# main.net
KiCad netlist of a schematic drawn in EAGLE
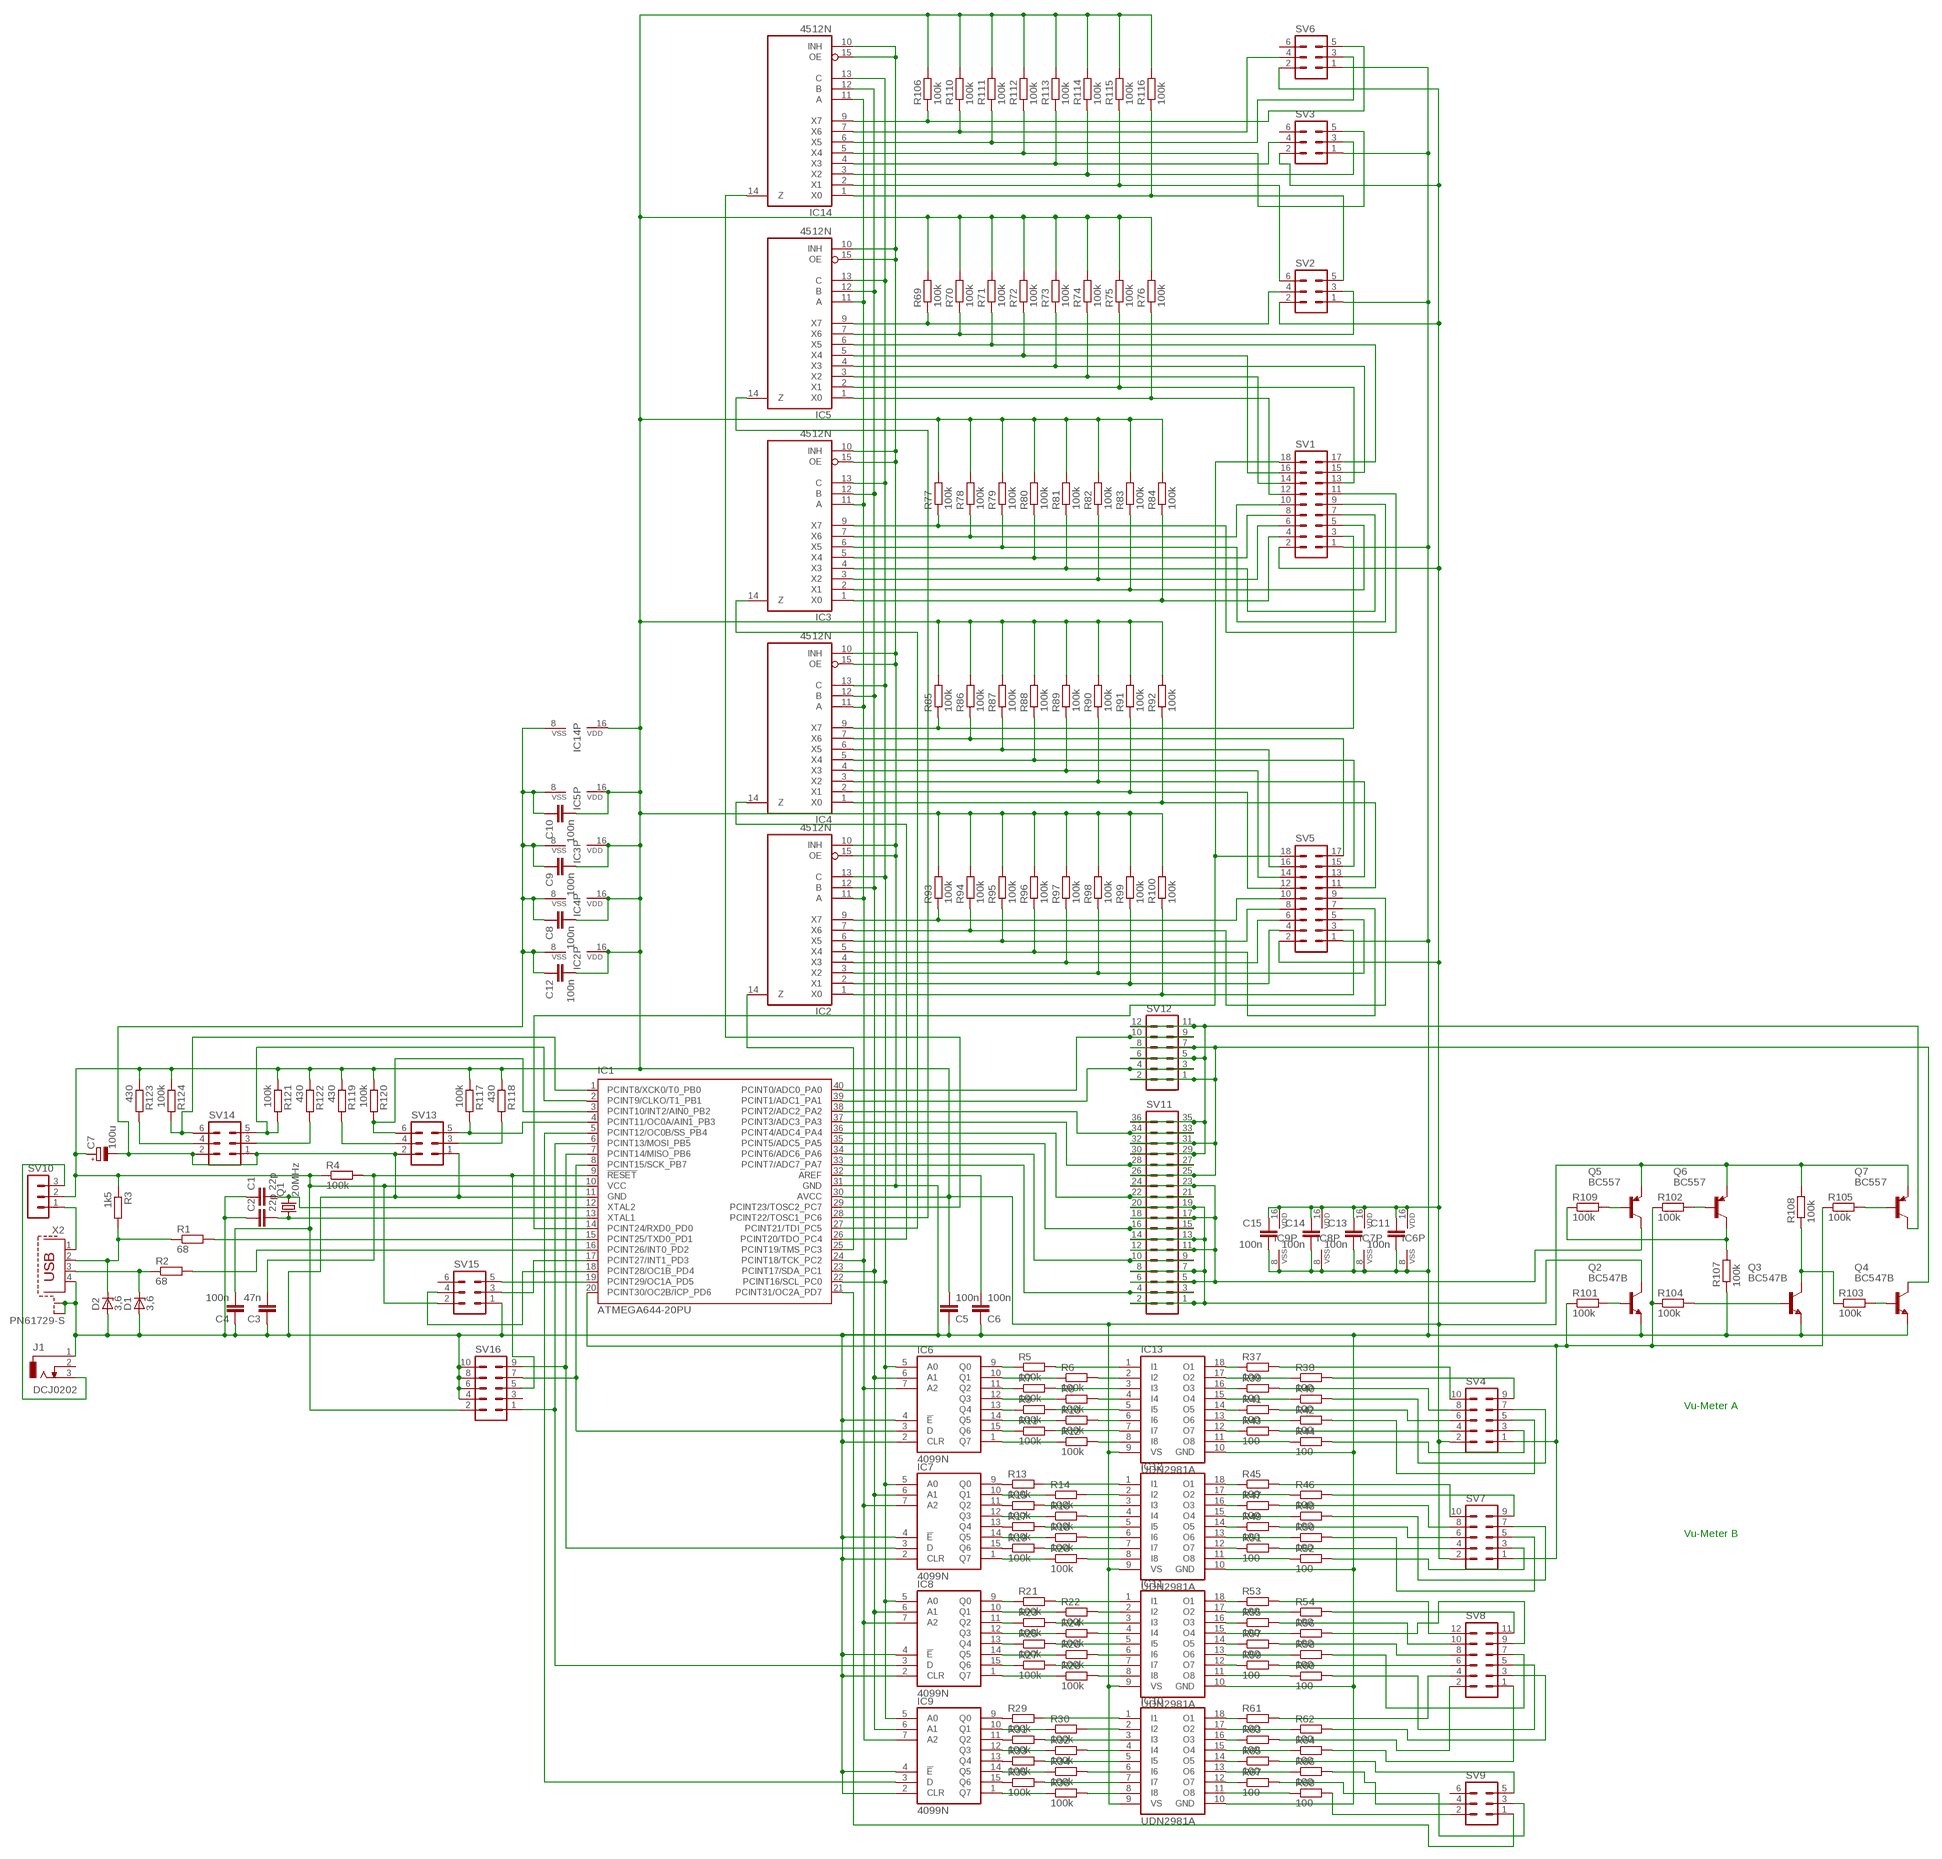
[diagram p0: schematic, sheet 1]

(export (version "E")
  (design (tool "Eeschema 10.0.6"))
  (components
    (comp (ref "C1")
      (value "22p")
      (footprint "eagle-import:C025-024X044")
      (libsource (lib "eagle-import") (part "C-EU025-024X044"))
    )
    (comp (ref "C2")
      (value "22p")
      (footprint "eagle-import:C025-024X044")
      (libsource (lib "eagle-import") (part "C-EU025-024X044"))
    )
    (comp (ref "C3")
      (value "47n")
      (footprint "eagle-import:C025-024X044")
      (libsource (lib "eagle-import") (part "C-EU025-024X044"))
    )
    (comp (ref "C4")
      (value "100n")
      (footprint "eagle-import:C025-024X044")
      (libsource (lib "eagle-import") (part "C-EU025-024X044"))
    )
    (comp (ref "C5")
      (value "100n")
      (footprint "eagle-import:C025-024X044")
      (libsource (lib "eagle-import") (part "C-EU025-024X044"))
    )
    (comp (ref "C6")
      (value "100n")
      (footprint "eagle-import:C025-024X044")
      (libsource (lib "eagle-import") (part "C-EU025-024X044"))
    )
    (comp (ref "C7")
      (value "100u")
      (footprint "eagle-import:E3,5-8")
      (libsource (lib "eagle-import") (part "CPOL-EUE3.5-8"))
    )
    (comp (ref "C8")
      (value "100n")
      (footprint "eagle-import:C025-024X044")
      (libsource (lib "eagle-import") (part "C-EU025-024X044"))
    )
    (comp (ref "C9")
      (value "100n")
      (footprint "eagle-import:C025-024X044")
      (libsource (lib "eagle-import") (part "C-EU025-024X044"))
    )
    (comp (ref "C10")
      (value "100n")
      (footprint "eagle-import:C025-024X044")
      (libsource (lib "eagle-import") (part "C-EU025-024X044"))
    )
    (comp (ref "C11")
      (value "100n")
      (footprint "eagle-import:C025-024X044")
      (libsource (lib "eagle-import") (part "C-EU025-024X044"))
    )
    (comp (ref "C12")
      (value "100n")
      (footprint "eagle-import:C025-024X044")
      (libsource (lib "eagle-import") (part "C-EU025-024X044"))
    )
    (comp (ref "C13")
      (value "100n")
      (footprint "eagle-import:C025-024X044")
      (libsource (lib "eagle-import") (part "C-EU025-024X044"))
    )
    (comp (ref "C14")
      (value "100n")
      (footprint "eagle-import:C025-024X044")
      (libsource (lib "eagle-import") (part "C-EU025-024X044"))
    )
    (comp (ref "C15")
      (value "100n")
      (footprint "eagle-import:C025-024X044")
      (libsource (lib "eagle-import") (part "C-EU025-024X044"))
    )
    (comp (ref "D1")
      (value "3,6")
      (footprint "eagle-import:DO34Z7")
      (libsource (lib "eagle-import") (part "ZENER-DIODEDO34-7"))
    )
    (comp (ref "D2")
      (value "3,6")
      (footprint "eagle-import:DO34Z7")
      (libsource (lib "eagle-import") (part "ZENER-DIODEDO34-7"))
    )
    (comp (ref "IC1")
      (value "ATMEGA644-20PU")
      (footprint "eagle-import:DIL40")
      (libsource (lib "eagle-import") (part "ATMEGA644-PU20"))
    )
    (comp (ref "IC2")
      (value "4512N")
      (footprint "eagle-import:DIL16")
      (libsource (lib "eagle-import") (part "4512N"))
    )
    (comp (ref "IC3")
      (value "4512N")
      (footprint "eagle-import:DIL16")
      (libsource (lib "eagle-import") (part "4512N"))
    )
    (comp (ref "IC4")
      (value "4512N")
      (footprint "eagle-import:DIL16")
      (libsource (lib "eagle-import") (part "4512N"))
    )
    (comp (ref "IC5")
      (value "4512N")
      (footprint "eagle-import:DIL16")
      (libsource (lib "eagle-import") (part "4512N"))
    )
    (comp (ref "IC6")
      (value "4099N")
      (footprint "eagle-import:DIL16")
      (libsource (lib "eagle-import") (part "4099N"))
    )
    (comp (ref "IC7")
      (value "4099N")
      (footprint "eagle-import:DIL16")
      (libsource (lib "eagle-import") (part "4099N"))
    )
    (comp (ref "IC8")
      (value "4099N")
      (footprint "eagle-import:DIL16")
      (libsource (lib "eagle-import") (part "4099N"))
    )
    (comp (ref "IC9")
      (value "4099N")
      (footprint "eagle-import:DIL16")
      (libsource (lib "eagle-import") (part "4099N"))
    )
    (comp (ref "IC10")
      (value "UDN2981A")
      (footprint "eagle-import:DIL18")
      (libsource (lib "eagle-import") (part "UDN298A1"))
    )
    (comp (ref "IC11")
      (value "UDN2981A")
      (footprint "eagle-import:DIL18")
      (libsource (lib "eagle-import") (part "UDN298A1"))
    )
    (comp (ref "IC12")
      (value "UDN2981A")
      (footprint "eagle-import:DIL18")
      (libsource (lib "eagle-import") (part "UDN298A1"))
    )
    (comp (ref "IC13")
      (value "UDN2981A")
      (footprint "eagle-import:DIL18")
      (libsource (lib "eagle-import") (part "UDN298A1"))
    )
    (comp (ref "IC14")
      (value "4512N")
      (footprint "eagle-import:DIL16")
      (libsource (lib "eagle-import") (part "4512N"))
    )
    (comp (ref "J1")
      (value "DCJ0202")
      (footprint "eagle-import:DCJ0202")
      (libsource (lib "eagle-import") (part "DCJ0202"))
    )
    (comp (ref "Q1")
      (value "20MHz")
      (footprint "eagle-import:HC18U-V")
      (libsource (lib "eagle-import") (part "CRYSTALHC18U-V"))
    )
    (comp (ref "Q2")
      (value "BC547B")
      (footprint "eagle-import:TO92")
      (libsource (lib "eagle-import") (part "BC547B"))
    )
    (comp (ref "Q3")
      (value "BC547B")
      (footprint "eagle-import:TO92")
      (libsource (lib "eagle-import") (part "BC547B"))
    )
    (comp (ref "Q4")
      (value "BC547B")
      (footprint "eagle-import:TO92")
      (libsource (lib "eagle-import") (part "BC547B"))
    )
    (comp (ref "Q5")
      (value "BC557")
      (footprint "eagle-import:TO92")
      (libsource (lib "eagle-import") (part "BC557"))
    )
    (comp (ref "Q6")
      (value "BC557")
      (footprint "eagle-import:TO92")
      (libsource (lib "eagle-import") (part "BC557"))
    )
    (comp (ref "Q7")
      (value "BC557")
      (footprint "eagle-import:TO92")
      (libsource (lib "eagle-import") (part "BC557"))
    )
    (comp (ref "R1")
      (value "68")
      (footprint "eagle-import:0204_7")
      (libsource (lib "eagle-import") (part "R-EU_0204/7"))
    )
    (comp (ref "R2")
      (value "68")
      (footprint "eagle-import:0204_7")
      (libsource (lib "eagle-import") (part "R-EU_0204/7"))
    )
    (comp (ref "R3")
      (value "1k5")
      (footprint "eagle-import:0204_7")
      (libsource (lib "eagle-import") (part "R-EU_0204/7"))
    )
    (comp (ref "R4")
      (value "100k")
      (footprint "eagle-import:0204_7")
      (libsource (lib "eagle-import") (part "R-EU_0204/7"))
    )
    (comp (ref "R5")
      (value "100k")
      (footprint "eagle-import:0204_7")
      (libsource (lib "eagle-import") (part "R-EU_0204/7"))
    )
    (comp (ref "R6")
      (value "100k")
      (footprint "eagle-import:0204_7")
      (libsource (lib "eagle-import") (part "R-EU_0204/7"))
    )
    (comp (ref "R7")
      (value "100k")
      (footprint "eagle-import:0204_7")
      (libsource (lib "eagle-import") (part "R-EU_0204/7"))
    )
    (comp (ref "R8")
      (value "100k")
      (footprint "eagle-import:0204_7")
      (libsource (lib "eagle-import") (part "R-EU_0204/7"))
    )
    (comp (ref "R9")
      (value "100k")
      (footprint "eagle-import:0204_7")
      (libsource (lib "eagle-import") (part "R-EU_0204/7"))
    )
    (comp (ref "R10")
      (value "100k")
      (footprint "eagle-import:0204_7")
      (libsource (lib "eagle-import") (part "R-EU_0204/7"))
    )
    (comp (ref "R11")
      (value "100k")
      (footprint "eagle-import:0204_7")
      (libsource (lib "eagle-import") (part "R-EU_0204/7"))
    )
    (comp (ref "R12")
      (value "100k")
      (footprint "eagle-import:0204_7")
      (libsource (lib "eagle-import") (part "R-EU_0204/7"))
    )
    (comp (ref "R13")
      (value "100k")
      (footprint "eagle-import:0204_7")
      (libsource (lib "eagle-import") (part "R-EU_0204/7"))
    )
    (comp (ref "R14")
      (value "100k")
      (footprint "eagle-import:0204_7")
      (libsource (lib "eagle-import") (part "R-EU_0204/7"))
    )
    (comp (ref "R15")
      (value "100k")
      (footprint "eagle-import:0204_7")
      (libsource (lib "eagle-import") (part "R-EU_0204/7"))
    )
    (comp (ref "R16")
      (value "100k")
      (footprint "eagle-import:0204_7")
      (libsource (lib "eagle-import") (part "R-EU_0204/7"))
    )
    (comp (ref "R17")
      (value "100k")
      (footprint "eagle-import:0204_7")
      (libsource (lib "eagle-import") (part "R-EU_0204/7"))
    )
    (comp (ref "R18")
      (value "100k")
      (footprint "eagle-import:0204_7")
      (libsource (lib "eagle-import") (part "R-EU_0204/7"))
    )
    (comp (ref "R19")
      (value "100k")
      (footprint "eagle-import:0204_7")
      (libsource (lib "eagle-import") (part "R-EU_0204/7"))
    )
    (comp (ref "R20")
      (value "100k")
      (footprint "eagle-import:0204_7")
      (libsource (lib "eagle-import") (part "R-EU_0204/7"))
    )
    (comp (ref "R21")
      (value "100k")
      (footprint "eagle-import:0204_7")
      (libsource (lib "eagle-import") (part "R-EU_0204/7"))
    )
    (comp (ref "R22")
      (value "100k")
      (footprint "eagle-import:0204_7")
      (libsource (lib "eagle-import") (part "R-EU_0204/7"))
    )
    (comp (ref "R23")
      (value "100k")
      (footprint "eagle-import:0204_7")
      (libsource (lib "eagle-import") (part "R-EU_0204/7"))
    )
    (comp (ref "R24")
      (value "100k")
      (footprint "eagle-import:0204_7")
      (libsource (lib "eagle-import") (part "R-EU_0204/7"))
    )
    (comp (ref "R25")
      (value "100k")
      (footprint "eagle-import:0204_7")
      (libsource (lib "eagle-import") (part "R-EU_0204/7"))
    )
    (comp (ref "R26")
      (value "100k")
      (footprint "eagle-import:0204_7")
      (libsource (lib "eagle-import") (part "R-EU_0204/7"))
    )
    (comp (ref "R27")
      (value "100k")
      (footprint "eagle-import:0204_7")
      (libsource (lib "eagle-import") (part "R-EU_0204/7"))
    )
    (comp (ref "R28")
      (value "100k")
      (footprint "eagle-import:0204_7")
      (libsource (lib "eagle-import") (part "R-EU_0204/7"))
    )
    (comp (ref "R29")
      (value "100k")
      (footprint "eagle-import:0204_7")
      (libsource (lib "eagle-import") (part "R-EU_0204/7"))
    )
    (comp (ref "R30")
      (value "100k")
      (footprint "eagle-import:0204_7")
      (libsource (lib "eagle-import") (part "R-EU_0204/7"))
    )
    (comp (ref "R31")
      (value "100k")
      (footprint "eagle-import:0204_7")
      (libsource (lib "eagle-import") (part "R-EU_0204/7"))
    )
    (comp (ref "R32")
      (value "100k")
      (footprint "eagle-import:0204_7")
      (libsource (lib "eagle-import") (part "R-EU_0204/7"))
    )
    (comp (ref "R33")
      (value "100k")
      (footprint "eagle-import:0204_7")
      (libsource (lib "eagle-import") (part "R-EU_0204/7"))
    )
    (comp (ref "R34")
      (value "100k")
      (footprint "eagle-import:0204_7")
      (libsource (lib "eagle-import") (part "R-EU_0204/7"))
    )
    (comp (ref "R35")
      (value "100k")
      (footprint "eagle-import:0204_7")
      (libsource (lib "eagle-import") (part "R-EU_0204/7"))
    )
    (comp (ref "R36")
      (value "100k")
      (footprint "eagle-import:0204_7")
      (libsource (lib "eagle-import") (part "R-EU_0204/7"))
    )
    (comp (ref "R37")
      (value "100")
      (footprint "eagle-import:0204_7")
      (libsource (lib "eagle-import") (part "R-EU_0204/7"))
    )
    (comp (ref "R38")
      (value "100")
      (footprint "eagle-import:0204_7")
      (libsource (lib "eagle-import") (part "R-EU_0204/7"))
    )
    (comp (ref "R39")
      (value "100")
      (footprint "eagle-import:0204_7")
      (libsource (lib "eagle-import") (part "R-EU_0204/7"))
    )
    (comp (ref "R40")
      (value "100")
      (footprint "eagle-import:0204_7")
      (libsource (lib "eagle-import") (part "R-EU_0204/7"))
    )
    (comp (ref "R41")
      (value "100")
      (footprint "eagle-import:0204_7")
      (libsource (lib "eagle-import") (part "R-EU_0204/7"))
    )
    (comp (ref "R42")
      (value "100")
      (footprint "eagle-import:0204_7")
      (libsource (lib "eagle-import") (part "R-EU_0204/7"))
    )
    (comp (ref "R43")
      (value "100")
      (footprint "eagle-import:0204_7")
      (libsource (lib "eagle-import") (part "R-EU_0204/7"))
    )
    (comp (ref "R44")
      (value "100")
      (footprint "eagle-import:0204_7")
      (libsource (lib "eagle-import") (part "R-EU_0204/7"))
    )
    (comp (ref "R45")
      (value "100")
      (footprint "eagle-import:0204_7")
      (libsource (lib "eagle-import") (part "R-EU_0204/7"))
    )
    (comp (ref "R46")
      (value "100")
      (footprint "eagle-import:0204_7")
      (libsource (lib "eagle-import") (part "R-EU_0204/7"))
    )
    (comp (ref "R47")
      (value "100")
      (footprint "eagle-import:0204_7")
      (libsource (lib "eagle-import") (part "R-EU_0204/7"))
    )
    (comp (ref "R48")
      (value "100")
      (footprint "eagle-import:0204_7")
      (libsource (lib "eagle-import") (part "R-EU_0204/7"))
    )
    (comp (ref "R49")
      (value "100")
      (footprint "eagle-import:0204_7")
      (libsource (lib "eagle-import") (part "R-EU_0204/7"))
    )
    (comp (ref "R50")
      (value "100")
      (footprint "eagle-import:0204_7")
      (libsource (lib "eagle-import") (part "R-EU_0204/7"))
    )
    (comp (ref "R51")
      (value "100")
      (footprint "eagle-import:0204_7")
      (libsource (lib "eagle-import") (part "R-EU_0204/7"))
    )
    (comp (ref "R52")
      (value "100")
      (footprint "eagle-import:0204_7")
      (libsource (lib "eagle-import") (part "R-EU_0204/7"))
    )
    (comp (ref "R53")
      (value "100")
      (footprint "eagle-import:0204_7")
      (libsource (lib "eagle-import") (part "R-EU_0204/7"))
    )
    (comp (ref "R54")
      (value "100")
      (footprint "eagle-import:0204_7")
      (libsource (lib "eagle-import") (part "R-EU_0204/7"))
    )
    (comp (ref "R55")
      (value "100")
      (footprint "eagle-import:0204_7")
      (libsource (lib "eagle-import") (part "R-EU_0204/7"))
    )
    (comp (ref "R56")
      (value "100")
      (footprint "eagle-import:0204_7")
      (libsource (lib "eagle-import") (part "R-EU_0204/7"))
    )
    (comp (ref "R57")
      (value "100")
      (footprint "eagle-import:0204_7")
      (libsource (lib "eagle-import") (part "R-EU_0204/7"))
    )
    (comp (ref "R58")
      (value "100")
      (footprint "eagle-import:0204_7")
      (libsource (lib "eagle-import") (part "R-EU_0204/7"))
    )
    (comp (ref "R59")
      (value "100")
      (footprint "eagle-import:0204_7")
      (libsource (lib "eagle-import") (part "R-EU_0204/7"))
    )
    (comp (ref "R60")
      (value "100")
      (footprint "eagle-import:0204_7")
      (libsource (lib "eagle-import") (part "R-EU_0204/7"))
    )
    (comp (ref "R61")
      (value "100")
      (footprint "eagle-import:0204_7")
      (libsource (lib "eagle-import") (part "R-EU_0204/7"))
    )
    (comp (ref "R62")
      (value "100")
      (footprint "eagle-import:0204_7")
      (libsource (lib "eagle-import") (part "R-EU_0204/7"))
    )
    (comp (ref "R63")
      (value "100")
      (footprint "eagle-import:0204_7")
      (libsource (lib "eagle-import") (part "R-EU_0204/7"))
    )
    (comp (ref "R64")
      (value "100")
      (footprint "eagle-import:0204_7")
      (libsource (lib "eagle-import") (part "R-EU_0204/7"))
    )
    (comp (ref "R65")
      (value "100")
      (footprint "eagle-import:0204_7")
      (libsource (lib "eagle-import") (part "R-EU_0204/7"))
    )
    (comp (ref "R66")
      (value "100")
      (footprint "eagle-import:0204_7")
      (libsource (lib "eagle-import") (part "R-EU_0204/7"))
    )
    (comp (ref "R67")
      (value "100")
      (footprint "eagle-import:0204_7")
      (libsource (lib "eagle-import") (part "R-EU_0204/7"))
    )
    (comp (ref "R68")
      (value "100")
      (footprint "eagle-import:0204_7")
      (libsource (lib "eagle-import") (part "R-EU_0204/7"))
    )
    (comp (ref "R69")
      (value "100k")
      (footprint "eagle-import:0204_7")
      (libsource (lib "eagle-import") (part "R-EU_0204/7"))
    )
    (comp (ref "R70")
      (value "100k")
      (footprint "eagle-import:0204_7")
      (libsource (lib "eagle-import") (part "R-EU_0204/7"))
    )
    (comp (ref "R71")
      (value "100k")
      (footprint "eagle-import:0204_7")
      (libsource (lib "eagle-import") (part "R-EU_0204/7"))
    )
    (comp (ref "R72")
      (value "100k")
      (footprint "eagle-import:0204_7")
      (libsource (lib "eagle-import") (part "R-EU_0204/7"))
    )
    (comp (ref "R73")
      (value "100k")
      (footprint "eagle-import:0204_7")
      (libsource (lib "eagle-import") (part "R-EU_0204/7"))
    )
    (comp (ref "R74")
      (value "100k")
      (footprint "eagle-import:0204_7")
      (libsource (lib "eagle-import") (part "R-EU_0204/7"))
    )
    (comp (ref "R75")
      (value "100k")
      (footprint "eagle-import:0204_7")
      (libsource (lib "eagle-import") (part "R-EU_0204/7"))
    )
    (comp (ref "R76")
      (value "100k")
      (footprint "eagle-import:0204_7")
      (libsource (lib "eagle-import") (part "R-EU_0204/7"))
    )
    (comp (ref "R77")
      (value "100k")
      (footprint "eagle-import:0204_7")
      (libsource (lib "eagle-import") (part "R-EU_0204/7"))
    )
    (comp (ref "R78")
      (value "100k")
      (footprint "eagle-import:0204_7")
      (libsource (lib "eagle-import") (part "R-EU_0204/7"))
    )
    (comp (ref "R79")
      (value "100k")
      (footprint "eagle-import:0204_7")
      (libsource (lib "eagle-import") (part "R-EU_0204/7"))
    )
    (comp (ref "R80")
      (value "100k")
      (footprint "eagle-import:0204_7")
      (libsource (lib "eagle-import") (part "R-EU_0204/7"))
    )
    (comp (ref "R81")
      (value "100k")
      (footprint "eagle-import:0204_7")
      (libsource (lib "eagle-import") (part "R-EU_0204/7"))
    )
    (comp (ref "R82")
      (value "100k")
      (footprint "eagle-import:0204_7")
      (libsource (lib "eagle-import") (part "R-EU_0204/7"))
    )
    (comp (ref "R83")
      (value "100k")
      (footprint "eagle-import:0204_7")
      (libsource (lib "eagle-import") (part "R-EU_0204/7"))
    )
    (comp (ref "R84")
      (value "100k")
      (footprint "eagle-import:0204_7")
      (libsource (lib "eagle-import") (part "R-EU_0204/7"))
    )
    (comp (ref "R85")
      (value "100k")
      (footprint "eagle-import:0204_7")
      (libsource (lib "eagle-import") (part "R-EU_0204/7"))
    )
    (comp (ref "R86")
      (value "100k")
      (footprint "eagle-import:0204_7")
      (libsource (lib "eagle-import") (part "R-EU_0204/7"))
    )
    (comp (ref "R87")
      (value "100k")
      (footprint "eagle-import:0204_7")
      (libsource (lib "eagle-import") (part "R-EU_0204/7"))
    )
    (comp (ref "R88")
      (value "100k")
      (footprint "eagle-import:0204_7")
      (libsource (lib "eagle-import") (part "R-EU_0204/7"))
    )
    (comp (ref "R89")
      (value "100k")
      (footprint "eagle-import:0204_7")
      (libsource (lib "eagle-import") (part "R-EU_0204/7"))
    )
    (comp (ref "R90")
      (value "100k")
      (footprint "eagle-import:0204_7")
      (libsource (lib "eagle-import") (part "R-EU_0204/7"))
    )
    (comp (ref "R91")
      (value "100k")
      (footprint "eagle-import:0204_7")
      (libsource (lib "eagle-import") (part "R-EU_0204/7"))
    )
    (comp (ref "R92")
      (value "100k")
      (footprint "eagle-import:0204_7")
      (libsource (lib "eagle-import") (part "R-EU_0204/7"))
    )
    (comp (ref "R93")
      (value "100k")
      (footprint "eagle-import:0204_7")
      (libsource (lib "eagle-import") (part "R-EU_0204/7"))
    )
    (comp (ref "R94")
      (value "100k")
      (footprint "eagle-import:0204_7")
      (libsource (lib "eagle-import") (part "R-EU_0204/7"))
    )
    (comp (ref "R95")
      (value "100k")
      (footprint "eagle-import:0204_7")
      (libsource (lib "eagle-import") (part "R-EU_0204/7"))
    )
    (comp (ref "R96")
      (value "100k")
      (footprint "eagle-import:0204_7")
      (libsource (lib "eagle-import") (part "R-EU_0204/7"))
    )
    (comp (ref "R97")
      (value "100k")
      (footprint "eagle-import:0204_7")
      (libsource (lib "eagle-import") (part "R-EU_0204/7"))
    )
    (comp (ref "R98")
      (value "100k")
      (footprint "eagle-import:0204_7")
      (libsource (lib "eagle-import") (part "R-EU_0204/7"))
    )
    (comp (ref "R99")
      (value "100k")
      (footprint "eagle-import:0204_7")
      (libsource (lib "eagle-import") (part "R-EU_0204/7"))
    )
    (comp (ref "R100")
      (value "100k")
      (footprint "eagle-import:0204_7")
      (libsource (lib "eagle-import") (part "R-EU_0204/7"))
    )
    (comp (ref "R101")
      (value "100k")
      (footprint "eagle-import:0204_7")
      (libsource (lib "eagle-import") (part "R-EU_0204/7"))
    )
    (comp (ref "R102")
      (value "100k")
      (footprint "eagle-import:0204_7")
      (libsource (lib "eagle-import") (part "R-EU_0204/7"))
    )
    (comp (ref "R103")
      (value "100k")
      (footprint "eagle-import:0204_7")
      (libsource (lib "eagle-import") (part "R-EU_0204/7"))
    )
    (comp (ref "R104")
      (value "100k")
      (footprint "eagle-import:0204_7")
      (libsource (lib "eagle-import") (part "R-EU_0204/7"))
    )
    (comp (ref "R105")
      (value "100k")
      (footprint "eagle-import:0204_7")
      (libsource (lib "eagle-import") (part "R-EU_0204/7"))
    )
    (comp (ref "R106")
      (value "100k")
      (footprint "eagle-import:0204_7")
      (libsource (lib "eagle-import") (part "R-EU_0204/7"))
    )
    (comp (ref "R107")
      (value "100k")
      (footprint "eagle-import:0204_7")
      (libsource (lib "eagle-import") (part "R-EU_0204/7"))
    )
    (comp (ref "R108")
      (value "100k")
      (footprint "eagle-import:0204_7")
      (libsource (lib "eagle-import") (part "R-EU_0204/7"))
    )
    (comp (ref "R109")
      (value "100k")
      (footprint "eagle-import:0204_7")
      (libsource (lib "eagle-import") (part "R-EU_0204/7"))
    )
    (comp (ref "R110")
      (value "100k")
      (footprint "eagle-import:0204_7")
      (libsource (lib "eagle-import") (part "R-EU_0204/7"))
    )
    (comp (ref "R111")
      (value "100k")
      (footprint "eagle-import:0204_7")
      (libsource (lib "eagle-import") (part "R-EU_0204/7"))
    )
    (comp (ref "R112")
      (value "100k")
      (footprint "eagle-import:0204_7")
      (libsource (lib "eagle-import") (part "R-EU_0204/7"))
    )
    (comp (ref "R113")
      (value "100k")
      (footprint "eagle-import:0204_7")
      (libsource (lib "eagle-import") (part "R-EU_0204/7"))
    )
    (comp (ref "R114")
      (value "100k")
      (footprint "eagle-import:0204_7")
      (libsource (lib "eagle-import") (part "R-EU_0204/7"))
    )
    (comp (ref "R115")
      (value "100k")
      (footprint "eagle-import:0204_7")
      (libsource (lib "eagle-import") (part "R-EU_0204/7"))
    )
    (comp (ref "R116")
      (value "100k")
      (footprint "eagle-import:0204_7")
      (libsource (lib "eagle-import") (part "R-EU_0204/7"))
    )
    (comp (ref "R117")
      (value "100k")
      (footprint "eagle-import:0204_7")
      (libsource (lib "eagle-import") (part "R-EU_0204/7"))
    )
    (comp (ref "R118")
      (value "430")
      (footprint "eagle-import:0204_7")
      (libsource (lib "eagle-import") (part "R-EU_0204/7"))
    )
    (comp (ref "R119")
      (value "430")
      (footprint "eagle-import:0204_7")
      (libsource (lib "eagle-import") (part "R-EU_0204/7"))
    )
    (comp (ref "R120")
      (value "100k")
      (footprint "eagle-import:0204_7")
      (libsource (lib "eagle-import") (part "R-EU_0204/7"))
    )
    (comp (ref "R121")
      (value "100k")
      (footprint "eagle-import:0204_7")
      (libsource (lib "eagle-import") (part "R-EU_0204/7"))
    )
    (comp (ref "R122")
      (value "430")
      (footprint "eagle-import:0204_7")
      (libsource (lib "eagle-import") (part "R-EU_0204/7"))
    )
    (comp (ref "R123")
      (value "430")
      (footprint "eagle-import:0204_7")
      (libsource (lib "eagle-import") (part "R-EU_0204/7"))
    )
    (comp (ref "R124")
      (value "100k")
      (footprint "eagle-import:0204_7")
      (libsource (lib "eagle-import") (part "R-EU_0204/7"))
    )
    (comp (ref "SV1")
      (value "MA09-2")
      (footprint "eagle-import:MA09-2")
      (libsource (lib "eagle-import") (part "MA09-2"))
    )
    (comp (ref "SV2")
      (value "MA03-2")
      (footprint "eagle-import:MA03-2")
      (libsource (lib "eagle-import") (part "MA03-2"))
    )
    (comp (ref "SV3")
      (value "MA03-2")
      (footprint "eagle-import:MA03-2")
      (libsource (lib "eagle-import") (part "MA03-2"))
    )
    (comp (ref "SV4")
      (value "MA05-2")
      (footprint "eagle-import:MA05-2")
      (libsource (lib "eagle-import") (part "MA05-2"))
    )
    (comp (ref "SV5")
      (value "MA09-2")
      (footprint "eagle-import:MA09-2")
      (libsource (lib "eagle-import") (part "MA09-2"))
    )
    (comp (ref "SV6")
      (value "MA03-2")
      (footprint "eagle-import:MA03-2")
      (libsource (lib "eagle-import") (part "MA03-2"))
    )
    (comp (ref "SV7")
      (value "MA05-2")
      (footprint "eagle-import:MA05-2")
      (libsource (lib "eagle-import") (part "MA05-2"))
    )
    (comp (ref "SV8")
      (value "MA06-2")
      (footprint "eagle-import:MA06-2")
      (libsource (lib "eagle-import") (part "MA06-2"))
    )
    (comp (ref "SV9")
      (value "MA03-2")
      (footprint "eagle-import:MA03-2")
      (libsource (lib "eagle-import") (part "MA03-2"))
    )
    (comp (ref "SV10")
      (value "MA03-1")
      (footprint "eagle-import:MA03-1")
      (libsource (lib "eagle-import") (part "MA03-1"))
    )
    (comp (ref "SV11")
      (value "MA18-2")
      (footprint "eagle-import:MA18-2")
      (libsource (lib "eagle-import") (part "MA18-2"))
    )
    (comp (ref "SV12")
      (value "MA06-2")
      (footprint "eagle-import:MA06-2")
      (libsource (lib "eagle-import") (part "MA06-2"))
    )
    (comp (ref "SV13")
      (value "MA03-2")
      (footprint "eagle-import:MA03-2")
      (libsource (lib "eagle-import") (part "MA03-2"))
    )
    (comp (ref "SV14")
      (value "MA03-2")
      (footprint "eagle-import:MA03-2")
      (libsource (lib "eagle-import") (part "MA03-2"))
    )
    (comp (ref "SV15")
      (value "MA03-2")
      (footprint "eagle-import:MA03-2")
      (libsource (lib "eagle-import") (part "MA03-2"))
    )
    (comp (ref "SV16")
      (value "MA05-2")
      (footprint "eagle-import:MA05-2")
      (libsource (lib "eagle-import") (part "MA05-2"))
    )
    (comp (ref "X2")
      (value "PN61729-S")
      (footprint "eagle-import:PN61729-S")
      (fields (field (name "OC_FARNELL") "unknown") (field (name "OC_NEWARK") "unknown"))
      (libsource (lib "eagle-import") (part "PN61729-S"))
    )
  )
  (nets
    (net (code "1") (name "Net-(D1-PadC)") (class "Default")
      (node (ref "D1") (pin "C") (pinfunction "C_C") (pintype "passive"))
      (node (ref "R2") (pin "1") (pinfunction "1_1") (pintype "passive"))
      (node (ref "X2") (pin "3") (pinfunction "3_3") (pintype "passive"))
    )
    (net (code "2") (name "Net-(D2-PadC)") (class "Default")
      (node (ref "D2") (pin "C") (pinfunction "C_C") (pintype "passive"))
      (node (ref "R1") (pin "1") (pinfunction "1_1") (pintype "passive"))
      (node (ref "R3") (pin "2") (pinfunction "2_2") (pintype "passive"))
      (node (ref "X2") (pin "2") (pinfunction "2_2") (pintype "passive"))
    )
    (net (code "3") (name "Net-(IC1-AREF)") (class "Default")
      (node (ref "C6") (pin "2") (pinfunction "2_2") (pintype "passive"))
      (node (ref "IC1") (pin "32") (pinfunction "AREF_32") (pintype "passive"))
    )
    (net (code "4") (name "Net-(IC1-AVCC)") (class "Default")
      (node (ref "C10") (pin "2") (pinfunction "2_2") (pintype "passive"))
      (node (ref "C11") (pin "1") (pinfunction "1_1") (pintype "passive"))
      (node (ref "C12") (pin "2") (pinfunction "2_2") (pintype "passive"))
      (node (ref "C13") (pin "1") (pinfunction "1_1") (pintype "passive"))
      (node (ref "C14") (pin "1") (pinfunction "1_1") (pintype "passive"))
      (node (ref "C15") (pin "1") (pinfunction "1_1") (pintype "passive"))
      (node (ref "C4") (pin "2") (pinfunction "2_2") (pintype "passive"))
      (node (ref "C5") (pin "2") (pinfunction "2_2") (pintype "passive"))
      (node (ref "C7") (pin "+") (pinfunction "+_+") (pintype "passive"))
      (node (ref "C8") (pin "2") (pinfunction "2_2") (pintype "passive"))
      (node (ref "C9") (pin "2") (pinfunction "2_2") (pintype "passive"))
      (node (ref "IC1") (pin "10") (pinfunction "VCC_10") (pintype "power_in"))
      (node (ref "IC1") (pin "30") (pinfunction "AVCC_30") (pintype "power_in"))
      (node (ref "IC10") (pin "9") (pinfunction "VS_9") (pintype "passive"))
      (node (ref "IC11") (pin "9") (pinfunction "VS_9") (pintype "passive"))
      (node (ref "IC12") (pin "9") (pinfunction "VS_9") (pintype "passive"))
      (node (ref "IC13") (pin "9") (pinfunction "VS_9") (pintype "passive"))
      (node (ref "IC14") (pin "16") (pinfunction "VDD_16") (pintype "power_in"))
      (node (ref "IC2") (pin "16") (pinfunction "VDD_16") (pintype "power_in"))
      (node (ref "IC3") (pin "16") (pinfunction "VDD_16") (pintype "power_in"))
      (node (ref "IC4") (pin "16") (pinfunction "VDD_16") (pintype "power_in"))
      (node (ref "IC5") (pin "16") (pinfunction "VDD_16") (pintype "power_in"))
      (node (ref "IC6") (pin "16") (pinfunction "VDD_16") (pintype "power_in"))
      (node (ref "IC7") (pin "16") (pinfunction "VDD_16") (pintype "power_in"))
      (node (ref "IC8") (pin "16") (pinfunction "VDD_16") (pintype "power_in"))
      (node (ref "IC9") (pin "16") (pinfunction "VDD_16") (pintype "power_in"))
      (node (ref "Q5") (pin "1") (pinfunction "E_1") (pintype "passive"))
      (node (ref "Q6") (pin "1") (pinfunction "E_1") (pintype "passive"))
      (node (ref "Q7") (pin "1") (pinfunction "E_1") (pintype "passive"))
      (node (ref "R100") (pin "2") (pinfunction "2_2") (pintype "passive"))
      (node (ref "R106") (pin "2") (pinfunction "2_2") (pintype "passive"))
      (node (ref "R108") (pin "2") (pinfunction "2_2") (pintype "passive"))
      (node (ref "R110") (pin "2") (pinfunction "2_2") (pintype "passive"))
      (node (ref "R111") (pin "2") (pinfunction "2_2") (pintype "passive"))
      (node (ref "R112") (pin "2") (pinfunction "2_2") (pintype "passive"))
      (node (ref "R113") (pin "2") (pinfunction "2_2") (pintype "passive"))
      (node (ref "R114") (pin "2") (pinfunction "2_2") (pintype "passive"))
      (node (ref "R115") (pin "2") (pinfunction "2_2") (pintype "passive"))
      (node (ref "R116") (pin "2") (pinfunction "2_2") (pintype "passive"))
      (node (ref "R117") (pin "1") (pinfunction "1_1") (pintype "passive"))
      (node (ref "R118") (pin "1") (pinfunction "1_1") (pintype "passive"))
      (node (ref "R119") (pin "1") (pinfunction "1_1") (pintype "passive"))
      (node (ref "R120") (pin "1") (pinfunction "1_1") (pintype "passive"))
      (node (ref "R121") (pin "1") (pinfunction "1_1") (pintype "passive"))
      (node (ref "R122") (pin "1") (pinfunction "1_1") (pintype "passive"))
      (node (ref "R123") (pin "1") (pinfunction "1_1") (pintype "passive"))
      (node (ref "R124") (pin "1") (pinfunction "1_1") (pintype "passive"))
      (node (ref "R3") (pin "1") (pinfunction "1_1") (pintype "passive"))
      (node (ref "R4") (pin "1") (pinfunction "1_1") (pintype "passive"))
      (node (ref "R69") (pin "2") (pinfunction "2_2") (pintype "passive"))
      (node (ref "R70") (pin "2") (pinfunction "2_2") (pintype "passive"))
      (node (ref "R71") (pin "2") (pinfunction "2_2") (pintype "passive"))
      (node (ref "R72") (pin "2") (pinfunction "2_2") (pintype "passive"))
      (node (ref "R73") (pin "2") (pinfunction "2_2") (pintype "passive"))
      (node (ref "R74") (pin "2") (pinfunction "2_2") (pintype "passive"))
      (node (ref "R75") (pin "2") (pinfunction "2_2") (pintype "passive"))
      (node (ref "R76") (pin "2") (pinfunction "2_2") (pintype "passive"))
      (node (ref "R77") (pin "2") (pinfunction "2_2") (pintype "passive"))
      (node (ref "R78") (pin "2") (pinfunction "2_2") (pintype "passive"))
      (node (ref "R79") (pin "2") (pinfunction "2_2") (pintype "passive"))
      (node (ref "R80") (pin "2") (pinfunction "2_2") (pintype "passive"))
      (node (ref "R81") (pin "2") (pinfunction "2_2") (pintype "passive"))
      (node (ref "R82") (pin "2") (pinfunction "2_2") (pintype "passive"))
      (node (ref "R83") (pin "2") (pinfunction "2_2") (pintype "passive"))
      (node (ref "R84") (pin "2") (pinfunction "2_2") (pintype "passive"))
      (node (ref "R85") (pin "2") (pinfunction "2_2") (pintype "passive"))
      (node (ref "R86") (pin "2") (pinfunction "2_2") (pintype "passive"))
      (node (ref "R87") (pin "2") (pinfunction "2_2") (pintype "passive"))
      (node (ref "R88") (pin "2") (pinfunction "2_2") (pintype "passive"))
      (node (ref "R89") (pin "2") (pinfunction "2_2") (pintype "passive"))
      (node (ref "R90") (pin "2") (pinfunction "2_2") (pintype "passive"))
      (node (ref "R91") (pin "2") (pinfunction "2_2") (pintype "passive"))
      (node (ref "R92") (pin "2") (pinfunction "2_2") (pintype "passive"))
      (node (ref "R93") (pin "2") (pinfunction "2_2") (pintype "passive"))
      (node (ref "R94") (pin "2") (pinfunction "2_2") (pintype "passive"))
      (node (ref "R95") (pin "2") (pinfunction "2_2") (pintype "passive"))
      (node (ref "R96") (pin "2") (pinfunction "2_2") (pintype "passive"))
      (node (ref "R97") (pin "2") (pinfunction "2_2") (pintype "passive"))
      (node (ref "R98") (pin "2") (pinfunction "2_2") (pintype "passive"))
      (node (ref "R99") (pin "2") (pinfunction "2_2") (pintype "passive"))
      (node (ref "SV1") (pin "2") (pinfunction "2_2") (pintype "passive"))
      (node (ref "SV10") (pin "2") (pinfunction "2_2") (pintype "passive"))
      (node (ref "SV15") (pin "2") (pinfunction "2_2") (pintype "passive"))
      (node (ref "SV16") (pin "2") (pinfunction "2_2") (pintype "passive"))
      (node (ref "SV2") (pin "2") (pinfunction "2_2") (pintype "passive"))
      (node (ref "SV3") (pin "2") (pinfunction "2_2") (pintype "passive"))
      (node (ref "SV4") (pin "2") (pinfunction "2_2") (pintype "passive"))
      (node (ref "SV5") (pin "2") (pinfunction "2_2") (pintype "passive"))
      (node (ref "SV6") (pin "2") (pinfunction "2_2") (pintype "passive"))
      (node (ref "SV7") (pin "2") (pinfunction "2_2") (pintype "passive"))
    )
    (net (code "5") (name "Net-(IC1-PCINT0{slash}ADC0_PA0)") (class "Default")
      (node (ref "IC1") (pin "40") (pinfunction "PCINT0/ADC0_PA0_40") (pintype "bidirectional"))
      (node (ref "SV12") (pin "10") (pinfunction "10_10") (pintype "passive"))
      (node (ref "SV12") (pin "9") (pinfunction "9_9") (pintype "passive"))
    )
    (net (code "6") (name "Net-(IC1-PCINT1{slash}ADC1_PA1)") (class "Default")
      (node (ref "IC1") (pin "39") (pinfunction "PCINT1/ADC1_PA1_39") (pintype "bidirectional"))
      (node (ref "SV12") (pin "3") (pinfunction "3_3") (pintype "passive"))
      (node (ref "SV12") (pin "4") (pinfunction "4_4") (pintype "passive"))
    )
    (net (code "7") (name "Net-(IC1-PCINT2{slash}ADC2_PA2)") (class "Default")
      (node (ref "IC1") (pin "38") (pinfunction "PCINT2/ADC2_PA2_38") (pintype "bidirectional"))
      (node (ref "SV11") (pin "33") (pinfunction "33_33") (pintype "passive"))
      (node (ref "SV11") (pin "34") (pinfunction "34_34") (pintype "passive"))
    )
    (net (code "8") (name "Net-(IC1-PCINT3{slash}ADC3_PA3)") (class "Default")
      (node (ref "IC1") (pin "37") (pinfunction "PCINT3/ADC3_PA3_37") (pintype "bidirectional"))
      (node (ref "SV11") (pin "27") (pinfunction "27_27") (pintype "passive"))
      (node (ref "SV11") (pin "28") (pinfunction "28_28") (pintype "passive"))
    )
    (net (code "9") (name "Net-(IC1-PCINT4{slash}ADC4_PA4)") (class "Default")
      (node (ref "IC1") (pin "36") (pinfunction "PCINT4/ADC4_PA4_36") (pintype "bidirectional"))
      (node (ref "SV11") (pin "21") (pinfunction "21_21") (pintype "passive"))
      (node (ref "SV11") (pin "22") (pinfunction "22_22") (pintype "passive"))
    )
    (net (code "10") (name "Net-(IC1-PCINT5{slash}ADC5_PA5)") (class "Default")
      (node (ref "IC1") (pin "35") (pinfunction "PCINT5/ADC5_PA5_35") (pintype "bidirectional"))
      (node (ref "SV11") (pin "15") (pinfunction "15_15") (pintype "passive"))
      (node (ref "SV11") (pin "16") (pinfunction "16_16") (pintype "passive"))
    )
    (net (code "11") (name "Net-(IC1-PCINT6{slash}ADC6_PA6)") (class "Default")
      (node (ref "IC1") (pin "34") (pinfunction "PCINT6/ADC6_PA6_34") (pintype "bidirectional"))
      (node (ref "SV11") (pin "10") (pinfunction "10_10") (pintype "passive"))
      (node (ref "SV11") (pin "9") (pinfunction "9_9") (pintype "passive"))
    )
    (net (code "12") (name "Net-(IC1-PCINT7{slash}ADC7_PA7)") (class "Default")
      (node (ref "IC1") (pin "33") (pinfunction "PCINT7/ADC7_PA7_33") (pintype "bidirectional"))
      (node (ref "SV11") (pin "3") (pinfunction "3_3") (pintype "passive"))
      (node (ref "SV11") (pin "4") (pinfunction "4_4") (pintype "passive"))
    )
    (net (code "13") (name "Net-(IC1-PCINT8{slash}XCK0{slash}T0_PB0)") (class "Default")
      (node (ref "IC1") (pin "1") (pinfunction "PCINT8/XCK0/T0_PB0_1") (pintype "bidirectional"))
      (node (ref "R124") (pin "2") (pinfunction "2_2") (pintype "passive"))
      (node (ref "SV14") (pin "6") (pinfunction "6_6") (pintype "passive"))
    )
    (net (code "14") (name "Net-(IC1-PCINT9{slash}CLKO{slash}T1_PB1)") (class "Default")
      (node (ref "IC1") (pin "2") (pinfunction "PCINT9/CLKO/T1_PB1_2") (pintype "bidirectional"))
      (node (ref "R121") (pin "2") (pinfunction "2_2") (pintype "passive"))
      (node (ref "SV14") (pin "5") (pinfunction "5_5") (pintype "passive"))
    )
    (net (code "15") (name "Net-(IC1-PCINT10{slash}INT2{slash}AIN0_PB2)") (class "Default")
      (node (ref "IC1") (pin "3") (pinfunction "PCINT10/INT2/AIN0_PB2_3") (pintype "bidirectional"))
      (node (ref "R120") (pin "2") (pinfunction "2_2") (pintype "passive"))
      (node (ref "SV13") (pin "6") (pinfunction "6_6") (pintype "passive"))
    )
    (net (code "16") (name "Net-(IC1-PCINT11{slash}OC0A{slash}AIN1_PB3)") (class "Default")
      (node (ref "IC1") (pin "4") (pinfunction "PCINT11/OC0A/AIN1_PB3_4") (pintype "bidirectional"))
      (node (ref "R117") (pin "2") (pinfunction "2_2") (pintype "passive"))
      (node (ref "SV13") (pin "5") (pinfunction "5_5") (pintype "passive"))
    )
    (net (code "17") (name "Net-(IC1-PCINT12{slash}OC0B{slash}SS_PB4)") (class "Default")
      (node (ref "IC1") (pin "5") (pinfunction "PCINT12/OC0B/SS_PB4_5") (pintype "bidirectional"))
      (node (ref "IC9") (pin "3") (pinfunction "D_3") (pintype "input"))
    )
    (net (code "18") (name "Net-(IC1-PCINT13{slash}MOSI_PB5)") (class "Default")
      (node (ref "IC1") (pin "6") (pinfunction "PCINT13/MOSI_PB5_6") (pintype "bidirectional"))
      (node (ref "IC8") (pin "3") (pinfunction "D_3") (pintype "input"))
      (node (ref "SV16") (pin "1") (pinfunction "1_1") (pintype "passive"))
    )
    (net (code "19") (name "Net-(IC1-PCINT14{slash}MISO_PB6)") (class "Default")
      (node (ref "IC1") (pin "7") (pinfunction "PCINT14/MISO_PB6_7") (pintype "bidirectional"))
      (node (ref "IC7") (pin "3") (pinfunction "D_3") (pintype "input"))
      (node (ref "SV16") (pin "9") (pinfunction "9_9") (pintype "passive"))
    )
    (net (code "20") (name "Net-(IC1-PCINT15{slash}SCK_PB7)") (class "Default")
      (node (ref "IC1") (pin "8") (pinfunction "PCINT15/SCK_PB7_8") (pintype "bidirectional"))
      (node (ref "IC6") (pin "3") (pinfunction "D_3") (pintype "input"))
      (node (ref "SV16") (pin "7") (pinfunction "7_7") (pintype "passive"))
    )
    (net (code "21") (name "Net-(IC1-PCINT16{slash}SCL_PC0)") (class "Default")
      (node (ref "IC1") (pin "22") (pinfunction "PCINT16/SCL_PC0_22") (pintype "bidirectional"))
      (node (ref "IC14") (pin "13") (pinfunction "C_13") (pintype "input"))
      (node (ref "IC2") (pin "13") (pinfunction "C_13") (pintype "input"))
      (node (ref "IC3") (pin "13") (pinfunction "C_13") (pintype "input"))
      (node (ref "IC4") (pin "13") (pinfunction "C_13") (pintype "input"))
      (node (ref "IC5") (pin "13") (pinfunction "C_13") (pintype "input"))
      (node (ref "IC6") (pin "5") (pinfunction "A0_5") (pintype "input"))
      (node (ref "IC7") (pin "5") (pinfunction "A0_5") (pintype "input"))
      (node (ref "IC8") (pin "5") (pinfunction "A0_5") (pintype "input"))
      (node (ref "IC9") (pin "5") (pinfunction "A0_5") (pintype "input"))
    )
    (net (code "22") (name "Net-(IC1-PCINT17{slash}SDA_PC1)") (class "Default")
      (node (ref "IC1") (pin "23") (pinfunction "PCINT17/SDA_PC1_23") (pintype "bidirectional"))
      (node (ref "IC14") (pin "12") (pinfunction "B_12") (pintype "input"))
      (node (ref "IC2") (pin "12") (pinfunction "B_12") (pintype "input"))
      (node (ref "IC3") (pin "12") (pinfunction "B_12") (pintype "input"))
      (node (ref "IC4") (pin "12") (pinfunction "B_12") (pintype "input"))
      (node (ref "IC5") (pin "12") (pinfunction "B_12") (pintype "input"))
      (node (ref "IC6") (pin "6") (pinfunction "A1_6") (pintype "input"))
      (node (ref "IC7") (pin "6") (pinfunction "A1_6") (pintype "input"))
      (node (ref "IC8") (pin "6") (pinfunction "A1_6") (pintype "input"))
      (node (ref "IC9") (pin "6") (pinfunction "A1_6") (pintype "input"))
    )
    (net (code "23") (name "Net-(IC1-PCINT18{slash}TCK_PC2)") (class "Default")
      (node (ref "IC1") (pin "24") (pinfunction "PCINT18/TCK_PC2_24") (pintype "bidirectional"))
      (node (ref "IC14") (pin "11") (pinfunction "A_11") (pintype "input"))
      (node (ref "IC2") (pin "11") (pinfunction "A_11") (pintype "input"))
      (node (ref "IC3") (pin "11") (pinfunction "A_11") (pintype "input"))
      (node (ref "IC4") (pin "11") (pinfunction "A_11") (pintype "input"))
      (node (ref "IC5") (pin "11") (pinfunction "A_11") (pintype "input"))
      (node (ref "IC6") (pin "7") (pinfunction "A2_7") (pintype "input"))
      (node (ref "IC7") (pin "7") (pinfunction "A2_7") (pintype "input"))
      (node (ref "IC8") (pin "7") (pinfunction "A2_7") (pintype "input"))
      (node (ref "IC9") (pin "7") (pinfunction "A2_7") (pintype "input"))
    )
    (net (code "24") (name "Net-(IC1-PCINT19{slash}TMS_PC3)") (class "Default")
      (node (ref "IC1") (pin "25") (pinfunction "PCINT19/TMS_PC3_25") (pintype "bidirectional"))
      (node (ref "IC2") (pin "14") (pinfunction "Z_14") (pintype "tri_state"))
    )
    (net (code "25") (name "Net-(IC1-PCINT20{slash}TDO_PC4)") (class "Default")
      (node (ref "IC1") (pin "26") (pinfunction "PCINT20/TDO_PC4_26") (pintype "bidirectional"))
      (node (ref "IC4") (pin "14") (pinfunction "Z_14") (pintype "tri_state"))
    )
    (net (code "26") (name "Net-(IC1-PCINT21{slash}TDI_PC5)") (class "Default")
      (node (ref "IC1") (pin "27") (pinfunction "PCINT21/TDI_PC5_27") (pintype "bidirectional"))
      (node (ref "IC3") (pin "14") (pinfunction "Z_14") (pintype "tri_state"))
    )
    (net (code "27") (name "Net-(IC1-PCINT22{slash}TOSC1_PC6)") (class "Default")
      (node (ref "IC1") (pin "28") (pinfunction "PCINT22/TOSC1_PC6_28") (pintype "bidirectional"))
      (node (ref "IC5") (pin "14") (pinfunction "Z_14") (pintype "tri_state"))
    )
    (net (code "28") (name "Net-(IC1-PCINT23{slash}TOSC2_PC7)") (class "Default")
      (node (ref "IC1") (pin "29") (pinfunction "PCINT23/TOSC2_PC7_29") (pintype "bidirectional"))
      (node (ref "IC14") (pin "14") (pinfunction "Z_14") (pintype "tri_state"))
    )
    (net (code "29") (name "Net-(IC1-PCINT24{slash}RXD0_PD0)") (class "Default")
      (node (ref "IC1") (pin "14") (pinfunction "PCINT24/RXD0_PD0_14") (pintype "bidirectional"))
      (node (ref "SV1") (pin "18") (pinfunction "18_18") (pintype "passive"))
      (node (ref "SV5") (pin "18") (pinfunction "18_18") (pintype "passive"))
    )
    (net (code "30") (name "Net-(IC1-PCINT25{slash}TXD0_PD1)") (class "Default")
      (node (ref "IC1") (pin "15") (pinfunction "PCINT25/TXD0_PD1_15") (pintype "bidirectional"))
      (node (ref "R1") (pin "2") (pinfunction "2_2") (pintype "passive"))
    )
    (net (code "31") (name "Net-(IC1-PCINT26{slash}INT0_PD2)") (class "Default")
      (node (ref "IC1") (pin "16") (pinfunction "PCINT26/INT0_PD2_16") (pintype "bidirectional"))
      (node (ref "R2") (pin "2") (pinfunction "2_2") (pintype "passive"))
    )
    (net (code "32") (name "Net-(IC1-PCINT27{slash}INT1_PD3)") (class "Default")
      (node (ref "IC1") (pin "17") (pinfunction "PCINT27/INT1_PD3_17") (pintype "bidirectional"))
      (node (ref "SV15") (pin "3") (pinfunction "3_3") (pintype "passive"))
    )
    (net (code "33") (name "Net-(IC1-PCINT28{slash}OC1B_PD4)") (class "Default")
      (node (ref "IC1") (pin "18") (pinfunction "PCINT28/OC1B_PD4_18") (pintype "bidirectional"))
      (node (ref "SV15") (pin "4") (pinfunction "4_4") (pintype "passive"))
    )
    (net (code "34") (name "Net-(IC1-PCINT29{slash}OC1A_PD5)") (class "Default")
      (node (ref "IC1") (pin "19") (pinfunction "PCINT29/OC1A_PD5_19") (pintype "bidirectional"))
      (node (ref "SV15") (pin "5") (pinfunction "5_5") (pintype "passive"))
    )
    (net (code "35") (name "Net-(IC1-PCINT30{slash}OC2B{slash}ICP_PD6)") (class "Default")
      (node (ref "IC1") (pin "20") (pinfunction "PCINT30/OC2B/ICP_PD6_20") (pintype "bidirectional"))
      (node (ref "R101") (pin "1") (pinfunction "1_1") (pintype "passive"))
      (node (ref "R102") (pin "1") (pinfunction "1_1") (pintype "passive"))
      (node (ref "R104") (pin "1") (pinfunction "1_1") (pintype "passive"))
      (node (ref "R105") (pin "1") (pinfunction "1_1") (pintype "passive"))
      (node (ref "SV4") (pin "1") (pinfunction "1_1") (pintype "passive"))
      (node (ref "SV7") (pin "1") (pinfunction "1_1") (pintype "passive"))
    )
    (net (code "36") (name "Net-(IC1-PCINT31{slash}OC2A_PD7)") (class "Default")
      (node (ref "IC1") (pin "21") (pinfunction "PCINT31/OC2A_PD7_21") (pintype "bidirectional"))
      (node (ref "SV9") (pin "1") (pinfunction "1_1") (pintype "passive"))
    )
    (net (code "37") (name "Net-(IC1-XTAL1)") (class "Default")
      (node (ref "C2") (pin "2") (pinfunction "2_2") (pintype "passive"))
      (node (ref "IC1") (pin "13") (pinfunction "XTAL1_13") (pintype "input"))
      (node (ref "Q1") (pin "1") (pinfunction "1_1") (pintype "passive"))
    )
    (net (code "38") (name "Net-(IC1-XTAL2)") (class "Default")
      (node (ref "C1") (pin "2") (pinfunction "2_2") (pintype "passive"))
      (node (ref "IC1") (pin "12") (pinfunction "XTAL2_12") (pintype "output"))
      (node (ref "Q1") (pin "2") (pinfunction "2_2") (pintype "passive"))
    )
    (net (code "39") (name "Net-(IC1-~{RESET})") (class "Default")
      (node (ref "C3") (pin "2") (pinfunction "2_2") (pintype "passive"))
      (node (ref "IC1") (pin "9") (pinfunction "~{RESET}_9") (pintype "input"))
      (node (ref "R4") (pin "2") (pinfunction "2_2") (pintype "passive"))
      (node (ref "SV16") (pin "5") (pinfunction "5_5") (pintype "passive"))
    )
    (net (code "40") (name "Net-(IC2A-X0)") (class "Default")
      (node (ref "IC2") (pin "1") (pinfunction "X0_1") (pintype "input"))
      (node (ref "R100") (pin "1") (pinfunction "1_1") (pintype "passive"))
      (node (ref "SV5") (pin "3") (pinfunction "3_3") (pintype "passive"))
    )
    (net (code "41") (name "Net-(IC2A-X1)") (class "Default")
      (node (ref "IC2") (pin "2") (pinfunction "X1_2") (pintype "input"))
      (node (ref "R99") (pin "1") (pinfunction "1_1") (pintype "passive"))
      (node (ref "SV5") (pin "4") (pinfunction "4_4") (pintype "passive"))
    )
    (net (code "42") (name "Net-(IC2A-X2)") (class "Default")
      (node (ref "IC2") (pin "3") (pinfunction "X2_3") (pintype "input"))
      (node (ref "R98") (pin "1") (pinfunction "1_1") (pintype "passive"))
      (node (ref "SV5") (pin "5") (pinfunction "5_5") (pintype "passive"))
    )
    (net (code "43") (name "Net-(IC2A-X3)") (class "Default")
      (node (ref "IC2") (pin "4") (pinfunction "X3_4") (pintype "input"))
      (node (ref "R97") (pin "1") (pinfunction "1_1") (pintype "passive"))
      (node (ref "SV5") (pin "6") (pinfunction "6_6") (pintype "passive"))
    )
    (net (code "44") (name "Net-(IC2A-X4)") (class "Default")
      (node (ref "IC2") (pin "5") (pinfunction "X4_5") (pintype "input"))
      (node (ref "R96") (pin "1") (pinfunction "1_1") (pintype "passive"))
      (node (ref "SV5") (pin "7") (pinfunction "7_7") (pintype "passive"))
    )
    (net (code "45") (name "Net-(IC2A-X5)") (class "Default")
      (node (ref "IC2") (pin "6") (pinfunction "X5_6") (pintype "input"))
      (node (ref "R95") (pin "1") (pinfunction "1_1") (pintype "passive"))
      (node (ref "SV5") (pin "8") (pinfunction "8_8") (pintype "passive"))
    )
    (net (code "46") (name "Net-(IC2A-X6)") (class "Default")
      (node (ref "IC2") (pin "7") (pinfunction "X6_7") (pintype "input"))
      (node (ref "R94") (pin "1") (pinfunction "1_1") (pintype "passive"))
      (node (ref "SV5") (pin "9") (pinfunction "9_9") (pintype "passive"))
    )
    (net (code "47") (name "Net-(IC2A-X7)") (class "Default")
      (node (ref "IC2") (pin "9") (pinfunction "X7_9") (pintype "input"))
      (node (ref "R93") (pin "1") (pinfunction "1_1") (pintype "passive"))
      (node (ref "SV5") (pin "10") (pinfunction "10_10") (pintype "passive"))
    )
    (net (code "48") (name "Net-(IC3A-X0)") (class "Default")
      (node (ref "IC3") (pin "1") (pinfunction "X0_1") (pintype "input"))
      (node (ref "R84") (pin "1") (pinfunction "1_1") (pintype "passive"))
      (node (ref "SV1") (pin "4") (pinfunction "4_4") (pintype "passive"))
    )
    (net (code "49") (name "Net-(IC3A-X1)") (class "Default")
      (node (ref "IC3") (pin "2") (pinfunction "X1_2") (pintype "input"))
      (node (ref "R83") (pin "1") (pinfunction "1_1") (pintype "passive"))
      (node (ref "SV1") (pin "5") (pinfunction "5_5") (pintype "passive"))
    )
    (net (code "50") (name "Net-(IC3A-X2)") (class "Default")
      (node (ref "IC3") (pin "3") (pinfunction "X2_3") (pintype "input"))
      (node (ref "R82") (pin "1") (pinfunction "1_1") (pintype "passive"))
      (node (ref "SV1") (pin "6") (pinfunction "6_6") (pintype "passive"))
    )
    (net (code "51") (name "Net-(IC3A-X3)") (class "Default")
      (node (ref "IC3") (pin "4") (pinfunction "X3_4") (pintype "input"))
      (node (ref "R81") (pin "1") (pinfunction "1_1") (pintype "passive"))
      (node (ref "SV1") (pin "7") (pinfunction "7_7") (pintype "passive"))
    )
    (net (code "52") (name "Net-(IC3A-X4)") (class "Default")
      (node (ref "IC3") (pin "5") (pinfunction "X4_5") (pintype "input"))
      (node (ref "R80") (pin "1") (pinfunction "1_1") (pintype "passive"))
      (node (ref "SV1") (pin "8") (pinfunction "8_8") (pintype "passive"))
    )
    (net (code "53") (name "Net-(IC3A-X5)") (class "Default")
      (node (ref "IC3") (pin "6") (pinfunction "X5_6") (pintype "input"))
      (node (ref "R79") (pin "1") (pinfunction "1_1") (pintype "passive"))
      (node (ref "SV1") (pin "9") (pinfunction "9_9") (pintype "passive"))
    )
    (net (code "54") (name "Net-(IC3A-X6)") (class "Default")
      (node (ref "IC3") (pin "7") (pinfunction "X6_7") (pintype "input"))
      (node (ref "R78") (pin "1") (pinfunction "1_1") (pintype "passive"))
      (node (ref "SV1") (pin "10") (pinfunction "10_10") (pintype "passive"))
    )
    (net (code "55") (name "Net-(IC3A-X7)") (class "Default")
      (node (ref "IC3") (pin "9") (pinfunction "X7_9") (pintype "input"))
      (node (ref "R77") (pin "1") (pinfunction "1_1") (pintype "passive"))
      (node (ref "SV1") (pin "11") (pinfunction "11_11") (pintype "passive"))
    )
    (net (code "56") (name "Net-(IC4A-X0)") (class "Default")
      (node (ref "IC4") (pin "1") (pinfunction "X0_1") (pintype "input"))
      (node (ref "R92") (pin "1") (pinfunction "1_1") (pintype "passive"))
      (node (ref "SV5") (pin "11") (pinfunction "11_11") (pintype "passive"))
    )
    (net (code "57") (name "Net-(IC4A-X1)") (class "Default")
      (node (ref "IC4") (pin "2") (pinfunction "X1_2") (pintype "input"))
      (node (ref "R91") (pin "1") (pinfunction "1_1") (pintype "passive"))
      (node (ref "SV5") (pin "12") (pinfunction "12_12") (pintype "passive"))
    )
    (net (code "58") (name "Net-(IC4A-X2)") (class "Default")
      (node (ref "IC4") (pin "3") (pinfunction "X2_3") (pintype "input"))
      (node (ref "R90") (pin "1") (pinfunction "1_1") (pintype "passive"))
      (node (ref "SV5") (pin "13") (pinfunction "13_13") (pintype "passive"))
    )
    (net (code "59") (name "Net-(IC4A-X3)") (class "Default")
      (node (ref "IC4") (pin "4") (pinfunction "X3_4") (pintype "input"))
      (node (ref "R89") (pin "1") (pinfunction "1_1") (pintype "passive"))
      (node (ref "SV5") (pin "14") (pinfunction "14_14") (pintype "passive"))
    )
    (net (code "60") (name "Net-(IC4A-X4)") (class "Default")
      (node (ref "IC4") (pin "5") (pinfunction "X4_5") (pintype "input"))
      (node (ref "R88") (pin "1") (pinfunction "1_1") (pintype "passive"))
      (node (ref "SV5") (pin "15") (pinfunction "15_15") (pintype "passive"))
    )
    (net (code "61") (name "Net-(IC4A-X5)") (class "Default")
      (node (ref "IC4") (pin "6") (pinfunction "X5_6") (pintype "input"))
      (node (ref "R87") (pin "1") (pinfunction "1_1") (pintype "passive"))
      (node (ref "SV5") (pin "16") (pinfunction "16_16") (pintype "passive"))
    )
    (net (code "62") (name "Net-(IC4A-X6)") (class "Default")
      (node (ref "IC4") (pin "7") (pinfunction "X6_7") (pintype "input"))
      (node (ref "R86") (pin "1") (pinfunction "1_1") (pintype "passive"))
      (node (ref "SV5") (pin "17") (pinfunction "17_17") (pintype "passive"))
    )
    (net (code "63") (name "Net-(IC4A-X7)") (class "Default")
      (node (ref "IC4") (pin "9") (pinfunction "X7_9") (pintype "input"))
      (node (ref "R85") (pin "1") (pinfunction "1_1") (pintype "passive"))
      (node (ref "SV1") (pin "3") (pinfunction "3_3") (pintype "passive"))
    )
    (net (code "64") (name "Net-(IC5A-X0)") (class "Default")
      (node (ref "IC5") (pin "1") (pinfunction "X0_1") (pintype "input"))
      (node (ref "R76") (pin "1") (pinfunction "1_1") (pintype "passive"))
      (node (ref "SV1") (pin "12") (pinfunction "12_12") (pintype "passive"))
    )
    (net (code "65") (name "Net-(IC5A-X1)") (class "Default")
      (node (ref "IC5") (pin "2") (pinfunction "X1_2") (pintype "input"))
      (node (ref "R75") (pin "1") (pinfunction "1_1") (pintype "passive"))
      (node (ref "SV1") (pin "13") (pinfunction "13_13") (pintype "passive"))
    )
    (net (code "66") (name "Net-(IC5A-X2)") (class "Default")
      (node (ref "IC5") (pin "3") (pinfunction "X2_3") (pintype "input"))
      (node (ref "R74") (pin "1") (pinfunction "1_1") (pintype "passive"))
      (node (ref "SV1") (pin "14") (pinfunction "14_14") (pintype "passive"))
    )
    (net (code "67") (name "Net-(IC5A-X3)") (class "Default")
      (node (ref "IC5") (pin "4") (pinfunction "X3_4") (pintype "input"))
      (node (ref "R73") (pin "1") (pinfunction "1_1") (pintype "passive"))
      (node (ref "SV1") (pin "15") (pinfunction "15_15") (pintype "passive"))
    )
    (net (code "68") (name "Net-(IC5A-X4)") (class "Default")
      (node (ref "IC5") (pin "5") (pinfunction "X4_5") (pintype "input"))
      (node (ref "R72") (pin "1") (pinfunction "1_1") (pintype "passive"))
      (node (ref "SV1") (pin "16") (pinfunction "16_16") (pintype "passive"))
    )
    (net (code "69") (name "Net-(IC5A-X5)") (class "Default")
      (node (ref "IC5") (pin "6") (pinfunction "X5_6") (pintype "input"))
      (node (ref "R71") (pin "1") (pinfunction "1_1") (pintype "passive"))
      (node (ref "SV1") (pin "17") (pinfunction "17_17") (pintype "passive"))
    )
    (net (code "70") (name "Net-(IC5A-X6)") (class "Default")
      (node (ref "IC5") (pin "7") (pinfunction "X6_7") (pintype "input"))
      (node (ref "R70") (pin "1") (pinfunction "1_1") (pintype "passive"))
      (node (ref "SV2") (pin "3") (pinfunction "3_3") (pintype "passive"))
    )
    (net (code "71") (name "Net-(IC5A-X7)") (class "Default")
      (node (ref "IC5") (pin "9") (pinfunction "X7_9") (pintype "input"))
      (node (ref "R69") (pin "1") (pinfunction "1_1") (pintype "passive"))
      (node (ref "SV2") (pin "4") (pinfunction "4_4") (pintype "passive"))
    )
    (net (code "72") (name "Net-(IC6A-Q0)") (class "Default")
      (node (ref "IC6") (pin "9") (pinfunction "Q0_9") (pintype "output"))
      (node (ref "R5") (pin "1") (pinfunction "1_1") (pintype "passive"))
    )
    (net (code "73") (name "Net-(IC6A-Q1)") (class "Default")
      (node (ref "IC6") (pin "10") (pinfunction "Q1_10") (pintype "output"))
      (node (ref "R6") (pin "1") (pinfunction "1_1") (pintype "passive"))
    )
    (net (code "74") (name "Net-(IC6A-Q2)") (class "Default")
      (node (ref "IC6") (pin "11") (pinfunction "Q2_11") (pintype "output"))
      (node (ref "R7") (pin "1") (pinfunction "1_1") (pintype "passive"))
    )
    (net (code "75") (name "Net-(IC6A-Q3)") (class "Default")
      (node (ref "IC6") (pin "12") (pinfunction "Q3_12") (pintype "output"))
      (node (ref "R8") (pin "1") (pinfunction "1_1") (pintype "passive"))
    )
    (net (code "76") (name "Net-(IC6A-Q4)") (class "Default")
      (node (ref "IC6") (pin "13") (pinfunction "Q4_13") (pintype "output"))
      (node (ref "R9") (pin "1") (pinfunction "1_1") (pintype "passive"))
    )
    (net (code "77") (name "Net-(IC6A-Q5)") (class "Default")
      (node (ref "IC6") (pin "14") (pinfunction "Q5_14") (pintype "output"))
      (node (ref "R10") (pin "1") (pinfunction "1_1") (pintype "passive"))
    )
    (net (code "78") (name "Net-(IC6A-Q6)") (class "Default")
      (node (ref "IC6") (pin "15") (pinfunction "Q6_15") (pintype "output"))
      (node (ref "R11") (pin "1") (pinfunction "1_1") (pintype "passive"))
    )
    (net (code "79") (name "Net-(IC6A-Q7)") (class "Default")
      (node (ref "IC6") (pin "1") (pinfunction "Q7_1") (pintype "output"))
      (node (ref "R12") (pin "1") (pinfunction "1_1") (pintype "passive"))
    )
    (net (code "80") (name "Net-(IC7A-Q0)") (class "Default")
      (node (ref "IC7") (pin "9") (pinfunction "Q0_9") (pintype "output"))
      (node (ref "R13") (pin "1") (pinfunction "1_1") (pintype "passive"))
    )
    (net (code "81") (name "Net-(IC7A-Q1)") (class "Default")
      (node (ref "IC7") (pin "10") (pinfunction "Q1_10") (pintype "output"))
      (node (ref "R14") (pin "1") (pinfunction "1_1") (pintype "passive"))
    )
    (net (code "82") (name "Net-(IC7A-Q2)") (class "Default")
      (node (ref "IC7") (pin "11") (pinfunction "Q2_11") (pintype "output"))
      (node (ref "R15") (pin "1") (pinfunction "1_1") (pintype "passive"))
    )
    (net (code "83") (name "Net-(IC7A-Q3)") (class "Default")
      (node (ref "IC7") (pin "12") (pinfunction "Q3_12") (pintype "output"))
      (node (ref "R16") (pin "1") (pinfunction "1_1") (pintype "passive"))
    )
    (net (code "84") (name "Net-(IC7A-Q4)") (class "Default")
      (node (ref "IC7") (pin "13") (pinfunction "Q4_13") (pintype "output"))
      (node (ref "R17") (pin "1") (pinfunction "1_1") (pintype "passive"))
    )
    (net (code "85") (name "Net-(IC7A-Q5)") (class "Default")
      (node (ref "IC7") (pin "14") (pinfunction "Q5_14") (pintype "output"))
      (node (ref "R18") (pin "1") (pinfunction "1_1") (pintype "passive"))
    )
    (net (code "86") (name "Net-(IC7A-Q6)") (class "Default")
      (node (ref "IC7") (pin "15") (pinfunction "Q6_15") (pintype "output"))
      (node (ref "R19") (pin "1") (pinfunction "1_1") (pintype "passive"))
    )
    (net (code "87") (name "Net-(IC7A-Q7)") (class "Default")
      (node (ref "IC7") (pin "1") (pinfunction "Q7_1") (pintype "output"))
      (node (ref "R20") (pin "1") (pinfunction "1_1") (pintype "passive"))
    )
    (net (code "88") (name "Net-(IC8A-Q0)") (class "Default")
      (node (ref "IC8") (pin "9") (pinfunction "Q0_9") (pintype "output"))
      (node (ref "R21") (pin "1") (pinfunction "1_1") (pintype "passive"))
    )
    (net (code "89") (name "Net-(IC8A-Q1)") (class "Default")
      (node (ref "IC8") (pin "10") (pinfunction "Q1_10") (pintype "output"))
      (node (ref "R22") (pin "1") (pinfunction "1_1") (pintype "passive"))
    )
    (net (code "90") (name "Net-(IC8A-Q2)") (class "Default")
      (node (ref "IC8") (pin "11") (pinfunction "Q2_11") (pintype "output"))
      (node (ref "R23") (pin "1") (pinfunction "1_1") (pintype "passive"))
    )
    (net (code "91") (name "Net-(IC8A-Q3)") (class "Default")
      (node (ref "IC8") (pin "12") (pinfunction "Q3_12") (pintype "output"))
      (node (ref "R24") (pin "1") (pinfunction "1_1") (pintype "passive"))
    )
    (net (code "92") (name "Net-(IC8A-Q4)") (class "Default")
      (node (ref "IC8") (pin "13") (pinfunction "Q4_13") (pintype "output"))
      (node (ref "R25") (pin "1") (pinfunction "1_1") (pintype "passive"))
    )
    (net (code "93") (name "Net-(IC8A-Q5)") (class "Default")
      (node (ref "IC8") (pin "14") (pinfunction "Q5_14") (pintype "output"))
      (node (ref "R26") (pin "1") (pinfunction "1_1") (pintype "passive"))
    )
    (net (code "94") (name "Net-(IC8A-Q6)") (class "Default")
      (node (ref "IC8") (pin "15") (pinfunction "Q6_15") (pintype "output"))
      (node (ref "R27") (pin "1") (pinfunction "1_1") (pintype "passive"))
    )
    (net (code "95") (name "Net-(IC8A-Q7)") (class "Default")
      (node (ref "IC8") (pin "1") (pinfunction "Q7_1") (pintype "output"))
      (node (ref "R28") (pin "1") (pinfunction "1_1") (pintype "passive"))
    )
    (net (code "96") (name "Net-(IC9A-Q0)") (class "Default")
      (node (ref "IC9") (pin "9") (pinfunction "Q0_9") (pintype "output"))
      (node (ref "R29") (pin "1") (pinfunction "1_1") (pintype "passive"))
    )
    (net (code "97") (name "Net-(IC9A-Q1)") (class "Default")
      (node (ref "IC9") (pin "10") (pinfunction "Q1_10") (pintype "output"))
      (node (ref "R30") (pin "1") (pinfunction "1_1") (pintype "passive"))
    )
    (net (code "98") (name "Net-(IC9A-Q2)") (class "Default")
      (node (ref "IC9") (pin "11") (pinfunction "Q2_11") (pintype "output"))
      (node (ref "R31") (pin "1") (pinfunction "1_1") (pintype "passive"))
    )
    (net (code "99") (name "Net-(IC9A-Q3)") (class "Default")
      (node (ref "IC9") (pin "12") (pinfunction "Q3_12") (pintype "output"))
      (node (ref "R32") (pin "1") (pinfunction "1_1") (pintype "passive"))
    )
    (net (code "100") (name "Net-(IC9A-Q4)") (class "Default")
      (node (ref "IC9") (pin "13") (pinfunction "Q4_13") (pintype "output"))
      (node (ref "R33") (pin "1") (pinfunction "1_1") (pintype "passive"))
    )
    (net (code "101") (name "Net-(IC9A-Q5)") (class "Default")
      (node (ref "IC9") (pin "14") (pinfunction "Q5_14") (pintype "output"))
      (node (ref "R34") (pin "1") (pinfunction "1_1") (pintype "passive"))
    )
    (net (code "102") (name "Net-(IC9A-Q6)") (class "Default")
      (node (ref "IC9") (pin "15") (pinfunction "Q6_15") (pintype "output"))
      (node (ref "R35") (pin "1") (pinfunction "1_1") (pintype "passive"))
    )
    (net (code "103") (name "Net-(IC9A-Q7)") (class "Default")
      (node (ref "IC9") (pin "1") (pinfunction "Q7_1") (pintype "output"))
      (node (ref "R36") (pin "1") (pinfunction "1_1") (pintype "passive"))
    )
    (net (code "104") (name "Net-(IC10-GND)") (class "Default")
      (node (ref "C1") (pin "1") (pinfunction "1_1") (pintype "passive"))
      (node (ref "C10") (pin "1") (pinfunction "1_1") (pintype "passive"))
      (node (ref "C11") (pin "2") (pinfunction "2_2") (pintype "passive"))
      (node (ref "C12") (pin "1") (pinfunction "1_1") (pintype "passive"))
      (node (ref "C13") (pin "2") (pinfunction "2_2") (pintype "passive"))
      (node (ref "C14") (pin "2") (pinfunction "2_2") (pintype "passive"))
      (node (ref "C15") (pin "2") (pinfunction "2_2") (pintype "passive"))
      (node (ref "C2") (pin "1") (pinfunction "1_1") (pintype "passive"))
      (node (ref "C3") (pin "1") (pinfunction "1_1") (pintype "passive"))
      (node (ref "C4") (pin "1") (pinfunction "1_1") (pintype "passive"))
      (node (ref "C5") (pin "1") (pinfunction "1_1") (pintype "passive"))
      (node (ref "C6") (pin "1") (pinfunction "1_1") (pintype "passive"))
      (node (ref "C7") (pin "-") (pinfunction "-_-") (pintype "passive"))
      (node (ref "C8") (pin "1") (pinfunction "1_1") (pintype "passive"))
      (node (ref "C9") (pin "1") (pinfunction "1_1") (pintype "passive"))
      (node (ref "D1") (pin "A") (pinfunction "A_A") (pintype "passive"))
      (node (ref "D2") (pin "A") (pinfunction "A_A") (pintype "passive"))
      (node (ref "IC1") (pin "11") (pinfunction "GND_11") (pintype "power_in"))
      (node (ref "IC1") (pin "31") (pinfunction "GND_31") (pintype "power_in"))
      (node (ref "IC10") (pin "10") (pinfunction "GND_10") (pintype "power_in"))
      (node (ref "IC11") (pin "10") (pinfunction "GND_10") (pintype "power_in"))
      (node (ref "IC12") (pin "10") (pinfunction "GND_10") (pintype "power_in"))
      (node (ref "IC13") (pin "10") (pinfunction "GND_10") (pintype "power_in"))
      (node (ref "IC14") (pin "10") (pinfunction "INH_10") (pintype "input"))
      (node (ref "IC14") (pin "15") (pinfunction "OE_15") (pintype "input"))
      (node (ref "IC14") (pin "8") (pinfunction "VSS_8") (pintype "power_in"))
      (node (ref "IC2") (pin "10") (pinfunction "INH_10") (pintype "input"))
      (node (ref "IC2") (pin "15") (pinfunction "OE_15") (pintype "input"))
      (node (ref "IC2") (pin "8") (pinfunction "VSS_8") (pintype "power_in"))
      (node (ref "IC3") (pin "10") (pinfunction "INH_10") (pintype "input"))
      (node (ref "IC3") (pin "15") (pinfunction "OE_15") (pintype "input"))
      (node (ref "IC3") (pin "8") (pinfunction "VSS_8") (pintype "power_in"))
      (node (ref "IC4") (pin "10") (pinfunction "INH_10") (pintype "input"))
      (node (ref "IC4") (pin "15") (pinfunction "OE_15") (pintype "input"))
      (node (ref "IC4") (pin "8") (pinfunction "VSS_8") (pintype "power_in"))
      (node (ref "IC5") (pin "10") (pinfunction "INH_10") (pintype "input"))
      (node (ref "IC5") (pin "15") (pinfunction "OE_15") (pintype "input"))
      (node (ref "IC5") (pin "8") (pinfunction "VSS_8") (pintype "power_in"))
      (node (ref "IC6") (pin "2") (pinfunction "CLR_2") (pintype "input"))
      (node (ref "IC6") (pin "4") (pinfunction "~{E}_4") (pintype "input"))
      (node (ref "IC6") (pin "8") (pinfunction "VSS_8") (pintype "power_in"))
      (node (ref "IC7") (pin "2") (pinfunction "CLR_2") (pintype "input"))
      (node (ref "IC7") (pin "4") (pinfunction "~{E}_4") (pintype "input"))
      (node (ref "IC7") (pin "8") (pinfunction "VSS_8") (pintype "power_in"))
      (node (ref "IC8") (pin "2") (pinfunction "CLR_2") (pintype "input"))
      (node (ref "IC8") (pin "4") (pinfunction "~{E}_4") (pintype "input"))
      (node (ref "IC8") (pin "8") (pinfunction "VSS_8") (pintype "power_in"))
      (node (ref "IC9") (pin "2") (pinfunction "CLR_2") (pintype "input"))
      (node (ref "IC9") (pin "4") (pinfunction "~{E}_4") (pintype "input"))
      (node (ref "IC9") (pin "8") (pinfunction "VSS_8") (pintype "power_in"))
      (node (ref "J1") (pin "1") (pinfunction "1_1") (pintype "passive"))
      (node (ref "Q2") (pin "1") (pinfunction "E_1") (pintype "passive"))
      (node (ref "Q3") (pin "1") (pinfunction "E_1") (pintype "passive"))
      (node (ref "Q4") (pin "1") (pinfunction "E_1") (pintype "passive"))
      (node (ref "R107") (pin "1") (pinfunction "1_1") (pintype "passive"))
      (node (ref "SV1") (pin "1") (pinfunction "1_1") (pintype "passive"))
      (node (ref "SV13") (pin "1") (pinfunction "1_1") (pintype "passive"))
      (node (ref "SV13") (pin "2") (pinfunction "2_2") (pintype "passive"))
      (node (ref "SV14") (pin "1") (pinfunction "1_1") (pintype "passive"))
      (node (ref "SV14") (pin "2") (pinfunction "2_2") (pintype "passive"))
      (node (ref "SV15") (pin "1") (pinfunction "1_1") (pintype "passive"))
      (node (ref "SV16") (pin "10") (pinfunction "10_10") (pintype "passive"))
      (node (ref "SV16") (pin "4") (pinfunction "4_4") (pintype "passive"))
      (node (ref "SV16") (pin "6") (pinfunction "6_6") (pintype "passive"))
      (node (ref "SV16") (pin "8") (pinfunction "8_8") (pintype "passive"))
      (node (ref "SV2") (pin "1") (pinfunction "1_1") (pintype "passive"))
      (node (ref "SV3") (pin "1") (pinfunction "1_1") (pintype "passive"))
      (node (ref "SV5") (pin "1") (pinfunction "1_1") (pintype "passive"))
      (node (ref "SV6") (pin "1") (pinfunction "1_1") (pintype "passive"))
      (node (ref "X2") (pin "4") (pinfunction "4_4") (pintype "passive"))
      (node (ref "X2") (pin "S1") (pinfunction "S1_S1") (pintype "passive"))
      (node (ref "X2") (pin "S2") (pinfunction "S2_S2") (pintype "passive"))
    )
    (net (code "105") (name "Net-(IC10-I1)") (class "Default")
      (node (ref "IC10") (pin "1") (pinfunction "I1_1") (pintype "input"))
      (node (ref "R29") (pin "2") (pinfunction "2_2") (pintype "passive"))
    )
    (net (code "106") (name "Net-(IC10-I2)") (class "Default")
      (node (ref "IC10") (pin "2") (pinfunction "I2_2") (pintype "input"))
      (node (ref "R30") (pin "2") (pinfunction "2_2") (pintype "passive"))
    )
    (net (code "107") (name "Net-(IC10-I3)") (class "Default")
      (node (ref "IC10") (pin "3") (pinfunction "I3_3") (pintype "input"))
      (node (ref "R31") (pin "2") (pinfunction "2_2") (pintype "passive"))
    )
    (net (code "108") (name "Net-(IC10-I4)") (class "Default")
      (node (ref "IC10") (pin "4") (pinfunction "I4_4") (pintype "input"))
      (node (ref "R32") (pin "2") (pinfunction "2_2") (pintype "passive"))
    )
    (net (code "109") (name "Net-(IC10-I5)") (class "Default")
      (node (ref "IC10") (pin "5") (pinfunction "I5_5") (pintype "input"))
      (node (ref "R33") (pin "2") (pinfunction "2_2") (pintype "passive"))
    )
    (net (code "110") (name "Net-(IC10-I6)") (class "Default")
      (node (ref "IC10") (pin "6") (pinfunction "I6_6") (pintype "input"))
      (node (ref "R34") (pin "2") (pinfunction "2_2") (pintype "passive"))
    )
    (net (code "111") (name "Net-(IC10-I7)") (class "Default")
      (node (ref "IC10") (pin "7") (pinfunction "I7_7") (pintype "input"))
      (node (ref "R35") (pin "2") (pinfunction "2_2") (pintype "passive"))
    )
    (net (code "112") (name "Net-(IC10-I8)") (class "Default")
      (node (ref "IC10") (pin "8") (pinfunction "I8_8") (pintype "input"))
      (node (ref "R36") (pin "2") (pinfunction "2_2") (pintype "passive"))
    )
    (net (code "113") (name "Net-(IC10-O1)") (class "Default")
      (node (ref "IC10") (pin "18") (pinfunction "O1_18") (pintype "open_collector"))
      (node (ref "R61") (pin "1") (pinfunction "1_1") (pintype "passive"))
    )
    (net (code "114") (name "Net-(IC10-O2)") (class "Default")
      (node (ref "IC10") (pin "17") (pinfunction "O2_17") (pintype "open_collector"))
      (node (ref "R62") (pin "1") (pinfunction "1_1") (pintype "passive"))
    )
    (net (code "115") (name "Net-(IC10-O3)") (class "Default")
      (node (ref "IC10") (pin "16") (pinfunction "O3_16") (pintype "open_collector"))
      (node (ref "R63") (pin "1") (pinfunction "1_1") (pintype "passive"))
    )
    (net (code "116") (name "Net-(IC10-O4)") (class "Default")
      (node (ref "IC10") (pin "15") (pinfunction "O4_15") (pintype "open_collector"))
      (node (ref "R64") (pin "1") (pinfunction "1_1") (pintype "passive"))
    )
    (net (code "117") (name "Net-(IC10-O5)") (class "Default")
      (node (ref "IC10") (pin "14") (pinfunction "O5_14") (pintype "open_collector"))
      (node (ref "R65") (pin "1") (pinfunction "1_1") (pintype "passive"))
    )
    (net (code "118") (name "Net-(IC10-O6)") (class "Default")
      (node (ref "IC10") (pin "13") (pinfunction "O6_13") (pintype "open_collector"))
      (node (ref "R66") (pin "1") (pinfunction "1_1") (pintype "passive"))
    )
    (net (code "119") (name "Net-(IC10-O7)") (class "Default")
      (node (ref "IC10") (pin "12") (pinfunction "O7_12") (pintype "open_collector"))
      (node (ref "R67") (pin "1") (pinfunction "1_1") (pintype "passive"))
    )
    (net (code "120") (name "Net-(IC10-O8)") (class "Default")
      (node (ref "IC10") (pin "11") (pinfunction "O8_11") (pintype "open_collector"))
      (node (ref "R68") (pin "1") (pinfunction "1_1") (pintype "passive"))
    )
    (net (code "121") (name "Net-(IC11-I1)") (class "Default")
      (node (ref "IC11") (pin "1") (pinfunction "I1_1") (pintype "input"))
      (node (ref "R21") (pin "2") (pinfunction "2_2") (pintype "passive"))
    )
    (net (code "122") (name "Net-(IC11-I2)") (class "Default")
      (node (ref "IC11") (pin "2") (pinfunction "I2_2") (pintype "input"))
      (node (ref "R22") (pin "2") (pinfunction "2_2") (pintype "passive"))
    )
    (net (code "123") (name "Net-(IC11-I3)") (class "Default")
      (node (ref "IC11") (pin "3") (pinfunction "I3_3") (pintype "input"))
      (node (ref "R23") (pin "2") (pinfunction "2_2") (pintype "passive"))
    )
    (net (code "124") (name "Net-(IC11-I4)") (class "Default")
      (node (ref "IC11") (pin "4") (pinfunction "I4_4") (pintype "input"))
      (node (ref "R24") (pin "2") (pinfunction "2_2") (pintype "passive"))
    )
    (net (code "125") (name "Net-(IC11-I5)") (class "Default")
      (node (ref "IC11") (pin "5") (pinfunction "I5_5") (pintype "input"))
      (node (ref "R25") (pin "2") (pinfunction "2_2") (pintype "passive"))
    )
    (net (code "126") (name "Net-(IC11-I6)") (class "Default")
      (node (ref "IC11") (pin "6") (pinfunction "I6_6") (pintype "input"))
      (node (ref "R26") (pin "2") (pinfunction "2_2") (pintype "passive"))
    )
    (net (code "127") (name "Net-(IC11-I7)") (class "Default")
      (node (ref "IC11") (pin "7") (pinfunction "I7_7") (pintype "input"))
      (node (ref "R27") (pin "2") (pinfunction "2_2") (pintype "passive"))
    )
    (net (code "128") (name "Net-(IC11-I8)") (class "Default")
      (node (ref "IC11") (pin "8") (pinfunction "I8_8") (pintype "input"))
      (node (ref "R28") (pin "2") (pinfunction "2_2") (pintype "passive"))
    )
    (net (code "129") (name "Net-(IC11-O1)") (class "Default")
      (node (ref "IC11") (pin "18") (pinfunction "O1_18") (pintype "open_collector"))
      (node (ref "R53") (pin "1") (pinfunction "1_1") (pintype "passive"))
    )
    (net (code "130") (name "Net-(IC11-O2)") (class "Default")
      (node (ref "IC11") (pin "17") (pinfunction "O2_17") (pintype "open_collector"))
      (node (ref "R54") (pin "1") (pinfunction "1_1") (pintype "passive"))
    )
    (net (code "131") (name "Net-(IC11-O3)") (class "Default")
      (node (ref "IC11") (pin "16") (pinfunction "O3_16") (pintype "open_collector"))
      (node (ref "R55") (pin "1") (pinfunction "1_1") (pintype "passive"))
    )
    (net (code "132") (name "Net-(IC11-O4)") (class "Default")
      (node (ref "IC11") (pin "15") (pinfunction "O4_15") (pintype "open_collector"))
      (node (ref "R56") (pin "1") (pinfunction "1_1") (pintype "passive"))
    )
    (net (code "133") (name "Net-(IC11-O5)") (class "Default")
      (node (ref "IC11") (pin "14") (pinfunction "O5_14") (pintype "open_collector"))
      (node (ref "R57") (pin "1") (pinfunction "1_1") (pintype "passive"))
    )
    (net (code "134") (name "Net-(IC11-O6)") (class "Default")
      (node (ref "IC11") (pin "13") (pinfunction "O6_13") (pintype "open_collector"))
      (node (ref "R58") (pin "1") (pinfunction "1_1") (pintype "passive"))
    )
    (net (code "135") (name "Net-(IC11-O7)") (class "Default")
      (node (ref "IC11") (pin "12") (pinfunction "O7_12") (pintype "open_collector"))
      (node (ref "R59") (pin "1") (pinfunction "1_1") (pintype "passive"))
    )
    (net (code "136") (name "Net-(IC11-O8)") (class "Default")
      (node (ref "IC11") (pin "11") (pinfunction "O8_11") (pintype "open_collector"))
      (node (ref "R60") (pin "1") (pinfunction "1_1") (pintype "passive"))
    )
    (net (code "137") (name "Net-(IC12-I1)") (class "Default")
      (node (ref "IC12") (pin "1") (pinfunction "I1_1") (pintype "input"))
      (node (ref "R13") (pin "2") (pinfunction "2_2") (pintype "passive"))
    )
    (net (code "138") (name "Net-(IC12-I2)") (class "Default")
      (node (ref "IC12") (pin "2") (pinfunction "I2_2") (pintype "input"))
      (node (ref "R14") (pin "2") (pinfunction "2_2") (pintype "passive"))
    )
    (net (code "139") (name "Net-(IC12-I3)") (class "Default")
      (node (ref "IC12") (pin "3") (pinfunction "I3_3") (pintype "input"))
      (node (ref "R15") (pin "2") (pinfunction "2_2") (pintype "passive"))
    )
    (net (code "140") (name "Net-(IC12-I4)") (class "Default")
      (node (ref "IC12") (pin "4") (pinfunction "I4_4") (pintype "input"))
      (node (ref "R16") (pin "2") (pinfunction "2_2") (pintype "passive"))
    )
    (net (code "141") (name "Net-(IC12-I5)") (class "Default")
      (node (ref "IC12") (pin "5") (pinfunction "I5_5") (pintype "input"))
      (node (ref "R17") (pin "2") (pinfunction "2_2") (pintype "passive"))
    )
    (net (code "142") (name "Net-(IC12-I6)") (class "Default")
      (node (ref "IC12") (pin "6") (pinfunction "I6_6") (pintype "input"))
      (node (ref "R18") (pin "2") (pinfunction "2_2") (pintype "passive"))
    )
    (net (code "143") (name "Net-(IC12-I7)") (class "Default")
      (node (ref "IC12") (pin "7") (pinfunction "I7_7") (pintype "input"))
      (node (ref "R19") (pin "2") (pinfunction "2_2") (pintype "passive"))
    )
    (net (code "144") (name "Net-(IC12-I8)") (class "Default")
      (node (ref "IC12") (pin "8") (pinfunction "I8_8") (pintype "input"))
      (node (ref "R20") (pin "2") (pinfunction "2_2") (pintype "passive"))
    )
    (net (code "145") (name "Net-(IC12-O1)") (class "Default")
      (node (ref "IC12") (pin "18") (pinfunction "O1_18") (pintype "open_collector"))
      (node (ref "R45") (pin "1") (pinfunction "1_1") (pintype "passive"))
    )
    (net (code "146") (name "Net-(IC12-O2)") (class "Default")
      (node (ref "IC12") (pin "17") (pinfunction "O2_17") (pintype "open_collector"))
      (node (ref "R46") (pin "1") (pinfunction "1_1") (pintype "passive"))
    )
    (net (code "147") (name "Net-(IC12-O3)") (class "Default")
      (node (ref "IC12") (pin "16") (pinfunction "O3_16") (pintype "open_collector"))
      (node (ref "R47") (pin "1") (pinfunction "1_1") (pintype "passive"))
    )
    (net (code "148") (name "Net-(IC12-O4)") (class "Default")
      (node (ref "IC12") (pin "15") (pinfunction "O4_15") (pintype "open_collector"))
      (node (ref "R48") (pin "1") (pinfunction "1_1") (pintype "passive"))
    )
    (net (code "149") (name "Net-(IC12-O5)") (class "Default")
      (node (ref "IC12") (pin "14") (pinfunction "O5_14") (pintype "open_collector"))
      (node (ref "R49") (pin "1") (pinfunction "1_1") (pintype "passive"))
    )
    (net (code "150") (name "Net-(IC12-O6)") (class "Default")
      (node (ref "IC12") (pin "13") (pinfunction "O6_13") (pintype "open_collector"))
      (node (ref "R50") (pin "1") (pinfunction "1_1") (pintype "passive"))
    )
    (net (code "151") (name "Net-(IC12-O7)") (class "Default")
      (node (ref "IC12") (pin "12") (pinfunction "O7_12") (pintype "open_collector"))
      (node (ref "R51") (pin "1") (pinfunction "1_1") (pintype "passive"))
    )
    (net (code "152") (name "Net-(IC12-O8)") (class "Default")
      (node (ref "IC12") (pin "11") (pinfunction "O8_11") (pintype "open_collector"))
      (node (ref "R52") (pin "1") (pinfunction "1_1") (pintype "passive"))
    )
    (net (code "153") (name "Net-(IC13-I1)") (class "Default")
      (node (ref "IC13") (pin "1") (pinfunction "I1_1") (pintype "input"))
      (node (ref "R5") (pin "2") (pinfunction "2_2") (pintype "passive"))
    )
    (net (code "154") (name "Net-(IC13-I2)") (class "Default")
      (node (ref "IC13") (pin "2") (pinfunction "I2_2") (pintype "input"))
      (node (ref "R6") (pin "2") (pinfunction "2_2") (pintype "passive"))
    )
    (net (code "155") (name "Net-(IC13-I3)") (class "Default")
      (node (ref "IC13") (pin "3") (pinfunction "I3_3") (pintype "input"))
      (node (ref "R7") (pin "2") (pinfunction "2_2") (pintype "passive"))
    )
    (net (code "156") (name "Net-(IC13-I4)") (class "Default")
      (node (ref "IC13") (pin "4") (pinfunction "I4_4") (pintype "input"))
      (node (ref "R8") (pin "2") (pinfunction "2_2") (pintype "passive"))
    )
    (net (code "157") (name "Net-(IC13-I5)") (class "Default")
      (node (ref "IC13") (pin "5") (pinfunction "I5_5") (pintype "input"))
      (node (ref "R9") (pin "2") (pinfunction "2_2") (pintype "passive"))
    )
    (net (code "158") (name "Net-(IC13-I6)") (class "Default")
      (node (ref "IC13") (pin "6") (pinfunction "I6_6") (pintype "input"))
      (node (ref "R10") (pin "2") (pinfunction "2_2") (pintype "passive"))
    )
    (net (code "159") (name "Net-(IC13-I7)") (class "Default")
      (node (ref "IC13") (pin "7") (pinfunction "I7_7") (pintype "input"))
      (node (ref "R11") (pin "2") (pinfunction "2_2") (pintype "passive"))
    )
    (net (code "160") (name "Net-(IC13-I8)") (class "Default")
      (node (ref "IC13") (pin "8") (pinfunction "I8_8") (pintype "input"))
      (node (ref "R12") (pin "2") (pinfunction "2_2") (pintype "passive"))
    )
    (net (code "161") (name "Net-(IC13-O1)") (class "Default")
      (node (ref "IC13") (pin "18") (pinfunction "O1_18") (pintype "open_collector"))
      (node (ref "R37") (pin "1") (pinfunction "1_1") (pintype "passive"))
    )
    (net (code "162") (name "Net-(IC13-O2)") (class "Default")
      (node (ref "IC13") (pin "17") (pinfunction "O2_17") (pintype "open_collector"))
      (node (ref "R38") (pin "1") (pinfunction "1_1") (pintype "passive"))
    )
    (net (code "163") (name "Net-(IC13-O3)") (class "Default")
      (node (ref "IC13") (pin "16") (pinfunction "O3_16") (pintype "open_collector"))
      (node (ref "R39") (pin "1") (pinfunction "1_1") (pintype "passive"))
    )
    (net (code "164") (name "Net-(IC13-O4)") (class "Default")
      (node (ref "IC13") (pin "15") (pinfunction "O4_15") (pintype "open_collector"))
      (node (ref "R40") (pin "1") (pinfunction "1_1") (pintype "passive"))
    )
    (net (code "165") (name "Net-(IC13-O5)") (class "Default")
      (node (ref "IC13") (pin "14") (pinfunction "O5_14") (pintype "open_collector"))
      (node (ref "R41") (pin "1") (pinfunction "1_1") (pintype "passive"))
    )
    (net (code "166") (name "Net-(IC13-O6)") (class "Default")
      (node (ref "IC13") (pin "13") (pinfunction "O6_13") (pintype "open_collector"))
      (node (ref "R42") (pin "1") (pinfunction "1_1") (pintype "passive"))
    )
    (net (code "167") (name "Net-(IC13-O7)") (class "Default")
      (node (ref "IC13") (pin "12") (pinfunction "O7_12") (pintype "open_collector"))
      (node (ref "R43") (pin "1") (pinfunction "1_1") (pintype "passive"))
    )
    (net (code "168") (name "Net-(IC13-O8)") (class "Default")
      (node (ref "IC13") (pin "11") (pinfunction "O8_11") (pintype "open_collector"))
      (node (ref "R44") (pin "1") (pinfunction "1_1") (pintype "passive"))
    )
    (net (code "169") (name "Net-(IC14A-X0)") (class "Default")
      (node (ref "IC14") (pin "1") (pinfunction "X0_1") (pintype "input"))
      (node (ref "R116") (pin "1") (pinfunction "1_1") (pintype "passive"))
      (node (ref "SV2") (pin "5") (pinfunction "5_5") (pintype "passive"))
    )
    (net (code "170") (name "Net-(IC14A-X1)") (class "Default")
      (node (ref "IC14") (pin "2") (pinfunction "X1_2") (pintype "input"))
      (node (ref "R115") (pin "1") (pinfunction "1_1") (pintype "passive"))
      (node (ref "SV2") (pin "6") (pinfunction "6_6") (pintype "passive"))
    )
    (net (code "171") (name "Net-(IC14A-X2)") (class "Default")
      (node (ref "IC14") (pin "3") (pinfunction "X2_3") (pintype "input"))
      (node (ref "R114") (pin "1") (pinfunction "1_1") (pintype "passive"))
      (node (ref "SV3") (pin "3") (pinfunction "3_3") (pintype "passive"))
    )
    (net (code "172") (name "Net-(IC14A-X3)") (class "Default")
      (node (ref "IC14") (pin "4") (pinfunction "X3_4") (pintype "input"))
      (node (ref "R113") (pin "1") (pinfunction "1_1") (pintype "passive"))
      (node (ref "SV3") (pin "4") (pinfunction "4_4") (pintype "passive"))
    )
    (net (code "173") (name "Net-(IC14A-X4)") (class "Default")
      (node (ref "IC14") (pin "5") (pinfunction "X4_5") (pintype "input"))
      (node (ref "R112") (pin "1") (pinfunction "1_1") (pintype "passive"))
      (node (ref "SV3") (pin "5") (pinfunction "5_5") (pintype "passive"))
    )
    (net (code "174") (name "Net-(IC14A-X5)") (class "Default")
      (node (ref "IC14") (pin "6") (pinfunction "X5_6") (pintype "input"))
      (node (ref "R111") (pin "1") (pinfunction "1_1") (pintype "passive"))
      (node (ref "SV6") (pin "3") (pinfunction "3_3") (pintype "passive"))
    )
    (net (code "175") (name "Net-(IC14A-X6)") (class "Default")
      (node (ref "IC14") (pin "7") (pinfunction "X6_7") (pintype "input"))
      (node (ref "R110") (pin "1") (pinfunction "1_1") (pintype "passive"))
      (node (ref "SV6") (pin "4") (pinfunction "4_4") (pintype "passive"))
    )
    (net (code "176") (name "Net-(IC14A-X7)") (class "Default")
      (node (ref "IC14") (pin "9") (pinfunction "X7_9") (pintype "input"))
      (node (ref "R106") (pin "1") (pinfunction "1_1") (pintype "passive"))
      (node (ref "SV6") (pin "5") (pinfunction "5_5") (pintype "passive"))
    )
    (net (code "177") (name "Net-(J1-Pad3)") (class "Default")
      (node (ref "J1") (pin "3") (pinfunction "3_3") (pintype "passive"))
      (node (ref "SV10") (pin "3") (pinfunction "3_3") (pintype "passive"))
    )
    (net (code "178") (name "Net-(Q2-B)") (class "Default")
      (node (ref "Q2") (pin "2") (pinfunction "B_2") (pintype "passive"))
      (node (ref "R101") (pin "2") (pinfunction "2_2") (pintype "passive"))
    )
    (net (code "179") (name "Net-(Q2-C)") (class "Default")
      (node (ref "Q2") (pin "3") (pinfunction "C_3") (pintype "passive"))
      (node (ref "SV11") (pin "1") (pinfunction "1_1") (pintype "passive"))
      (node (ref "SV11") (pin "13") (pinfunction "13_13") (pintype "passive"))
      (node (ref "SV11") (pin "14") (pinfunction "14_14") (pintype "passive"))
      (node (ref "SV11") (pin "19") (pinfunction "19_19") (pintype "passive"))
      (node (ref "SV11") (pin "2") (pinfunction "2_2") (pintype "passive"))
      (node (ref "SV11") (pin "20") (pinfunction "20_20") (pintype "passive"))
      (node (ref "SV11") (pin "7") (pinfunction "7_7") (pintype "passive"))
      (node (ref "SV11") (pin "8") (pinfunction "8_8") (pintype "passive"))
    )
    (net (code "180") (name "Net-(Q3-B)") (class "Default")
      (node (ref "Q3") (pin "2") (pinfunction "B_2") (pintype "passive"))
      (node (ref "R104") (pin "2") (pinfunction "2_2") (pintype "passive"))
    )
    (net (code "181") (name "Net-(Q3-C)") (class "Default")
      (node (ref "Q3") (pin "3") (pinfunction "C_3") (pintype "passive"))
      (node (ref "R103") (pin "1") (pinfunction "1_1") (pintype "passive"))
      (node (ref "R108") (pin "1") (pinfunction "1_1") (pintype "passive"))
    )
    (net (code "182") (name "Net-(Q4-B)") (class "Default")
      (node (ref "Q4") (pin "2") (pinfunction "B_2") (pintype "passive"))
      (node (ref "R103") (pin "2") (pinfunction "2_2") (pintype "passive"))
    )
    (net (code "183") (name "Net-(Q4-C)") (class "Default")
      (node (ref "Q4") (pin "3") (pinfunction "C_3") (pintype "passive"))
      (node (ref "SV11") (pin "25") (pinfunction "25_25") (pintype "passive"))
      (node (ref "SV11") (pin "26") (pinfunction "26_26") (pintype "passive"))
      (node (ref "SV11") (pin "31") (pinfunction "31_31") (pintype "passive"))
      (node (ref "SV11") (pin "32") (pinfunction "32_32") (pintype "passive"))
      (node (ref "SV12") (pin "1") (pinfunction "1_1") (pintype "passive"))
      (node (ref "SV12") (pin "2") (pinfunction "2_2") (pintype "passive"))
      (node (ref "SV12") (pin "7") (pinfunction "7_7") (pintype "passive"))
      (node (ref "SV12") (pin "8") (pinfunction "8_8") (pintype "passive"))
    )
    (net (code "184") (name "Net-(Q5-B)") (class "Default")
      (node (ref "Q5") (pin "2") (pinfunction "B_2") (pintype "passive"))
      (node (ref "R109") (pin "2") (pinfunction "2_2") (pintype "passive"))
    )
    (net (code "185") (name "Net-(Q5-C)") (class "Default")
      (node (ref "Q5") (pin "3") (pinfunction "C_3") (pintype "passive"))
      (node (ref "SV11") (pin "11") (pinfunction "11_11") (pintype "passive"))
      (node (ref "SV11") (pin "12") (pinfunction "12_12") (pintype "passive"))
      (node (ref "SV11") (pin "17") (pinfunction "17_17") (pintype "passive"))
      (node (ref "SV11") (pin "18") (pinfunction "18_18") (pintype "passive"))
      (node (ref "SV11") (pin "23") (pinfunction "23_23") (pintype "passive"))
      (node (ref "SV11") (pin "24") (pinfunction "24_24") (pintype "passive"))
      (node (ref "SV11") (pin "5") (pinfunction "5_5") (pintype "passive"))
      (node (ref "SV11") (pin "6") (pinfunction "6_6") (pintype "passive"))
    )
    (net (code "186") (name "Net-(Q6-B)") (class "Default")
      (node (ref "Q6") (pin "2") (pinfunction "B_2") (pintype "passive"))
      (node (ref "R102") (pin "2") (pinfunction "2_2") (pintype "passive"))
    )
    (net (code "187") (name "Net-(Q6-C)") (class "Default")
      (node (ref "Q6") (pin "3") (pinfunction "C_3") (pintype "passive"))
      (node (ref "R107") (pin "2") (pinfunction "2_2") (pintype "passive"))
      (node (ref "R109") (pin "1") (pinfunction "1_1") (pintype "passive"))
    )
    (net (code "188") (name "Net-(Q7-B)") (class "Default")
      (node (ref "Q7") (pin "2") (pinfunction "B_2") (pintype "passive"))
      (node (ref "R105") (pin "2") (pinfunction "2_2") (pintype "passive"))
    )
    (net (code "189") (name "Net-(Q7-C)") (class "Default")
      (node (ref "Q7") (pin "3") (pinfunction "C_3") (pintype "passive"))
      (node (ref "SV11") (pin "29") (pinfunction "29_29") (pintype "passive"))
      (node (ref "SV11") (pin "30") (pinfunction "30_30") (pintype "passive"))
      (node (ref "SV11") (pin "35") (pinfunction "35_35") (pintype "passive"))
      (node (ref "SV11") (pin "36") (pinfunction "36_36") (pintype "passive"))
      (node (ref "SV12") (pin "11") (pinfunction "11_11") (pintype "passive"))
      (node (ref "SV12") (pin "12") (pinfunction "12_12") (pintype "passive"))
      (node (ref "SV12") (pin "5") (pinfunction "5_5") (pintype "passive"))
      (node (ref "SV12") (pin "6") (pinfunction "6_6") (pintype "passive"))
    )
    (net (code "190") (name "Net-(R37-Pad2)") (class "Default")
      (node (ref "R37") (pin "2") (pinfunction "2_2") (pintype "passive"))
      (node (ref "SV4") (pin "10") (pinfunction "10_10") (pintype "passive"))
    )
    (net (code "191") (name "Net-(R38-Pad2)") (class "Default")
      (node (ref "R38") (pin "2") (pinfunction "2_2") (pintype "passive"))
      (node (ref "SV4") (pin "9") (pinfunction "9_9") (pintype "passive"))
    )
    (net (code "192") (name "Net-(R39-Pad2)") (class "Default")
      (node (ref "R39") (pin "2") (pinfunction "2_2") (pintype "passive"))
      (node (ref "SV4") (pin "8") (pinfunction "8_8") (pintype "passive"))
    )
    (net (code "193") (name "Net-(R40-Pad2)") (class "Default")
      (node (ref "R40") (pin "2") (pinfunction "2_2") (pintype "passive"))
      (node (ref "SV4") (pin "7") (pinfunction "7_7") (pintype "passive"))
    )
    (net (code "194") (name "Net-(R41-Pad2)") (class "Default")
      (node (ref "R41") (pin "2") (pinfunction "2_2") (pintype "passive"))
      (node (ref "SV4") (pin "6") (pinfunction "6_6") (pintype "passive"))
    )
    (net (code "195") (name "Net-(R42-Pad2)") (class "Default")
      (node (ref "R42") (pin "2") (pinfunction "2_2") (pintype "passive"))
      (node (ref "SV4") (pin "5") (pinfunction "5_5") (pintype "passive"))
    )
    (net (code "196") (name "Net-(R43-Pad2)") (class "Default")
      (node (ref "R43") (pin "2") (pinfunction "2_2") (pintype "passive"))
      (node (ref "SV4") (pin "4") (pinfunction "4_4") (pintype "passive"))
    )
    (net (code "197") (name "Net-(R44-Pad2)") (class "Default")
      (node (ref "R44") (pin "2") (pinfunction "2_2") (pintype "passive"))
      (node (ref "SV4") (pin "3") (pinfunction "3_3") (pintype "passive"))
    )
    (net (code "198") (name "Net-(R45-Pad2)") (class "Default")
      (node (ref "R45") (pin "2") (pinfunction "2_2") (pintype "passive"))
      (node (ref "SV7") (pin "10") (pinfunction "10_10") (pintype "passive"))
    )
    (net (code "199") (name "Net-(R46-Pad2)") (class "Default")
      (node (ref "R46") (pin "2") (pinfunction "2_2") (pintype "passive"))
      (node (ref "SV7") (pin "9") (pinfunction "9_9") (pintype "passive"))
    )
    (net (code "200") (name "Net-(R47-Pad2)") (class "Default")
      (node (ref "R47") (pin "2") (pinfunction "2_2") (pintype "passive"))
      (node (ref "SV7") (pin "8") (pinfunction "8_8") (pintype "passive"))
    )
    (net (code "201") (name "Net-(R48-Pad2)") (class "Default")
      (node (ref "R48") (pin "2") (pinfunction "2_2") (pintype "passive"))
      (node (ref "SV7") (pin "7") (pinfunction "7_7") (pintype "passive"))
    )
    (net (code "202") (name "Net-(R49-Pad2)") (class "Default")
      (node (ref "R49") (pin "2") (pinfunction "2_2") (pintype "passive"))
      (node (ref "SV7") (pin "6") (pinfunction "6_6") (pintype "passive"))
    )
    (net (code "203") (name "Net-(R50-Pad2)") (class "Default")
      (node (ref "R50") (pin "2") (pinfunction "2_2") (pintype "passive"))
      (node (ref "SV7") (pin "5") (pinfunction "5_5") (pintype "passive"))
    )
    (net (code "204") (name "Net-(R51-Pad2)") (class "Default")
      (node (ref "R51") (pin "2") (pinfunction "2_2") (pintype "passive"))
      (node (ref "SV7") (pin "4") (pinfunction "4_4") (pintype "passive"))
    )
    (net (code "205") (name "Net-(R52-Pad2)") (class "Default")
      (node (ref "R52") (pin "2") (pinfunction "2_2") (pintype "passive"))
      (node (ref "SV7") (pin "3") (pinfunction "3_3") (pintype "passive"))
    )
    (net (code "206") (name "Net-(R53-Pad2)") (class "Default")
      (node (ref "R53") (pin "2") (pinfunction "2_2") (pintype "passive"))
      (node (ref "SV8") (pin "12") (pinfunction "12_12") (pintype "passive"))
    )
    (net (code "207") (name "Net-(R54-Pad2)") (class "Default")
      (node (ref "R54") (pin "2") (pinfunction "2_2") (pintype "passive"))
      (node (ref "SV8") (pin "11") (pinfunction "11_11") (pintype "passive"))
    )
    (net (code "208") (name "Net-(R55-Pad2)") (class "Default")
      (node (ref "R55") (pin "2") (pinfunction "2_2") (pintype "passive"))
      (node (ref "SV8") (pin "10") (pinfunction "10_10") (pintype "passive"))
    )
    (net (code "209") (name "Net-(R56-Pad2)") (class "Default")
      (node (ref "R56") (pin "2") (pinfunction "2_2") (pintype "passive"))
      (node (ref "SV8") (pin "9") (pinfunction "9_9") (pintype "passive"))
    )
    (net (code "210") (name "Net-(R57-Pad2)") (class "Default")
      (node (ref "R57") (pin "2") (pinfunction "2_2") (pintype "passive"))
      (node (ref "SV8") (pin "8") (pinfunction "8_8") (pintype "passive"))
    )
    (net (code "211") (name "Net-(R58-Pad2)") (class "Default")
      (node (ref "R58") (pin "2") (pinfunction "2_2") (pintype "passive"))
      (node (ref "SV8") (pin "7") (pinfunction "7_7") (pintype "passive"))
    )
    (net (code "212") (name "Net-(R59-Pad2)") (class "Default")
      (node (ref "R59") (pin "2") (pinfunction "2_2") (pintype "passive"))
      (node (ref "SV8") (pin "6") (pinfunction "6_6") (pintype "passive"))
    )
    (net (code "213") (name "Net-(R60-Pad2)") (class "Default")
      (node (ref "R60") (pin "2") (pinfunction "2_2") (pintype "passive"))
      (node (ref "SV8") (pin "5") (pinfunction "5_5") (pintype "passive"))
    )
    (net (code "214") (name "Net-(R61-Pad2)") (class "Default")
      (node (ref "R61") (pin "2") (pinfunction "2_2") (pintype "passive"))
      (node (ref "SV8") (pin "4") (pinfunction "4_4") (pintype "passive"))
    )
    (net (code "215") (name "Net-(R62-Pad2)") (class "Default")
      (node (ref "R62") (pin "2") (pinfunction "2_2") (pintype "passive"))
      (node (ref "SV8") (pin "3") (pinfunction "3_3") (pintype "passive"))
    )
    (net (code "216") (name "Net-(R63-Pad2)") (class "Default")
      (node (ref "R63") (pin "2") (pinfunction "2_2") (pintype "passive"))
      (node (ref "SV8") (pin "2") (pinfunction "2_2") (pintype "passive"))
    )
    (net (code "217") (name "Net-(R64-Pad2)") (class "Default")
      (node (ref "R64") (pin "2") (pinfunction "2_2") (pintype "passive"))
      (node (ref "SV8") (pin "1") (pinfunction "1_1") (pintype "passive"))
    )
    (net (code "218") (name "Net-(R65-Pad2)") (class "Default")
      (node (ref "R65") (pin "2") (pinfunction "2_2") (pintype "passive"))
      (node (ref "SV9") (pin "5") (pinfunction "5_5") (pintype "passive"))
    )
    (net (code "219") (name "Net-(R66-Pad2)") (class "Default")
      (node (ref "R66") (pin "2") (pinfunction "2_2") (pintype "passive"))
      (node (ref "SV9") (pin "4") (pinfunction "4_4") (pintype "passive"))
    )
    (net (code "220") (name "Net-(R67-Pad2)") (class "Default")
      (node (ref "R67") (pin "2") (pinfunction "2_2") (pintype "passive"))
      (node (ref "SV9") (pin "3") (pinfunction "3_3") (pintype "passive"))
    )
    (net (code "221") (name "Net-(R68-Pad2)") (class "Default")
      (node (ref "R68") (pin "2") (pinfunction "2_2") (pintype "passive"))
      (node (ref "SV9") (pin "2") (pinfunction "2_2") (pintype "passive"))
    )
    (net (code "222") (name "Net-(R118-Pad2)") (class "Default")
      (node (ref "R118") (pin "2") (pinfunction "2_2") (pintype "passive"))
      (node (ref "SV13") (pin "3") (pinfunction "3_3") (pintype "passive"))
    )
    (net (code "223") (name "Net-(R119-Pad2)") (class "Default")
      (node (ref "R119") (pin "2") (pinfunction "2_2") (pintype "passive"))
      (node (ref "SV13") (pin "4") (pinfunction "4_4") (pintype "passive"))
    )
    (net (code "224") (name "Net-(R122-Pad2)") (class "Default")
      (node (ref "R122") (pin "2") (pinfunction "2_2") (pintype "passive"))
      (node (ref "SV14") (pin "3") (pinfunction "3_3") (pintype "passive"))
    )
    (net (code "225") (name "Net-(R123-Pad2)") (class "Default")
      (node (ref "R123") (pin "2") (pinfunction "2_2") (pintype "passive"))
      (node (ref "SV14") (pin "4") (pinfunction "4_4") (pintype "passive"))
    )
    (net (code "226") (name "Net-(SV10-Pad1)") (class "Default")
      (node (ref "SV10") (pin "1") (pinfunction "1_1") (pintype "passive"))
      (node (ref "X2") (pin "1") (pinfunction "1_1") (pintype "passive"))
    )
    (net (code "227") (name "unconnected-(J1-Pad2)") (class "Default")
      (node (ref "J1") (pin "2") (pinfunction "2_2") (pintype "passive"))
    )
    (net (code "228") (name "unconnected-(SV3-Pad6)") (class "Default")
      (node (ref "SV3") (pin "6") (pinfunction "6_6") (pintype "passive"))
    )
    (net (code "229") (name "unconnected-(SV6-Pad6)") (class "Default")
      (node (ref "SV6") (pin "6") (pinfunction "6_6") (pintype "passive"))
    )
    (net (code "230") (name "unconnected-(SV9-Pad6)") (class "Default")
      (node (ref "SV9") (pin "6") (pinfunction "6_6") (pintype "passive"))
    )
    (net (code "231") (name "unconnected-(SV15-Pad6)") (class "Default")
      (node (ref "SV15") (pin "6") (pinfunction "6_6") (pintype "passive"))
    )
    (net (code "232") (name "unconnected-(SV16-Pad3)") (class "Default")
      (node (ref "SV16") (pin "3") (pinfunction "3_3") (pintype "passive"))
    )
  )
)
